# Iridium_9603_Beacon_V5M.net
KiCad netlist of a schematic drawn in EAGLE
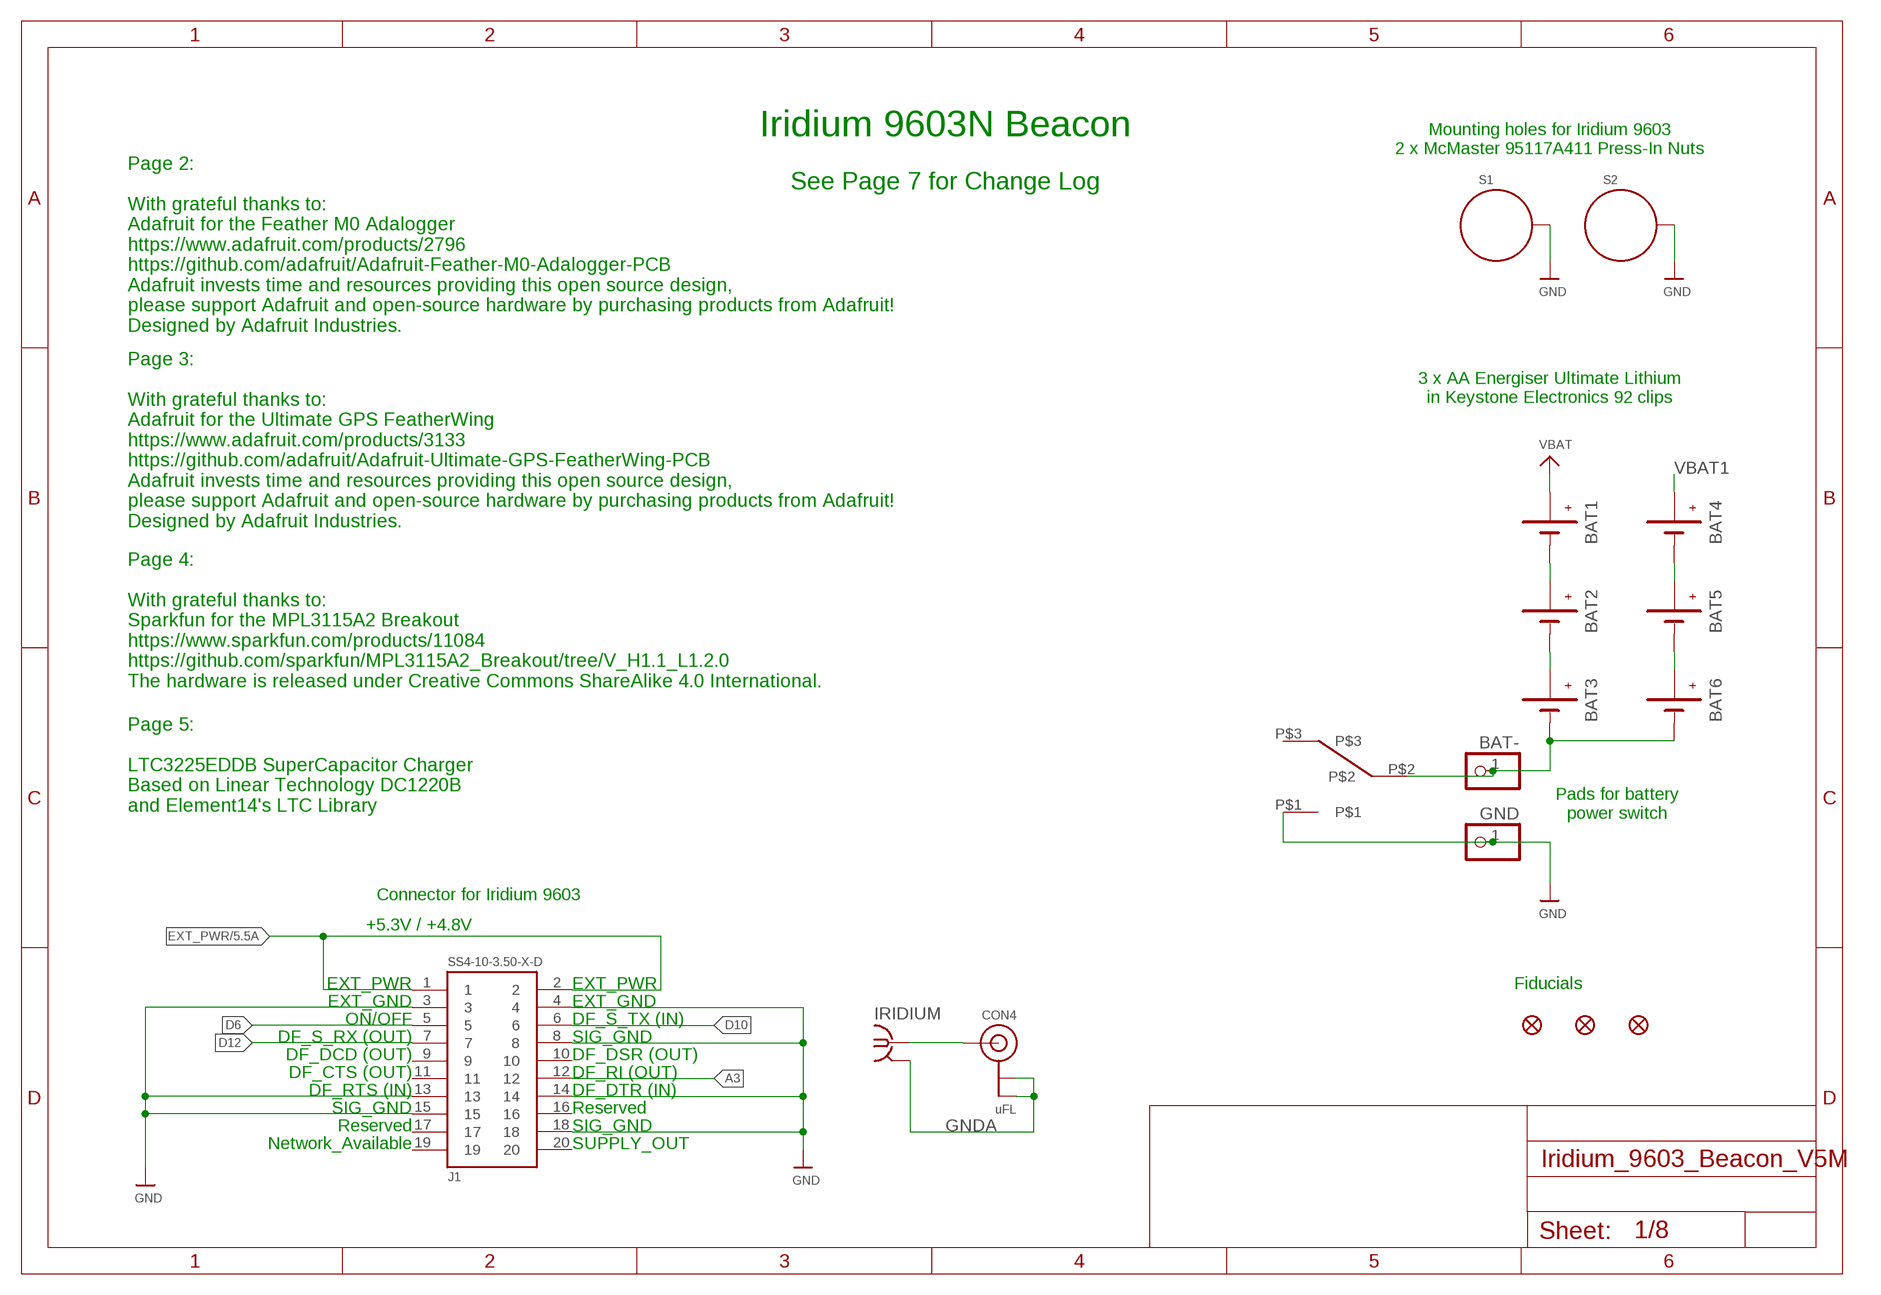
[diagram p0: schematic, sheet 1]
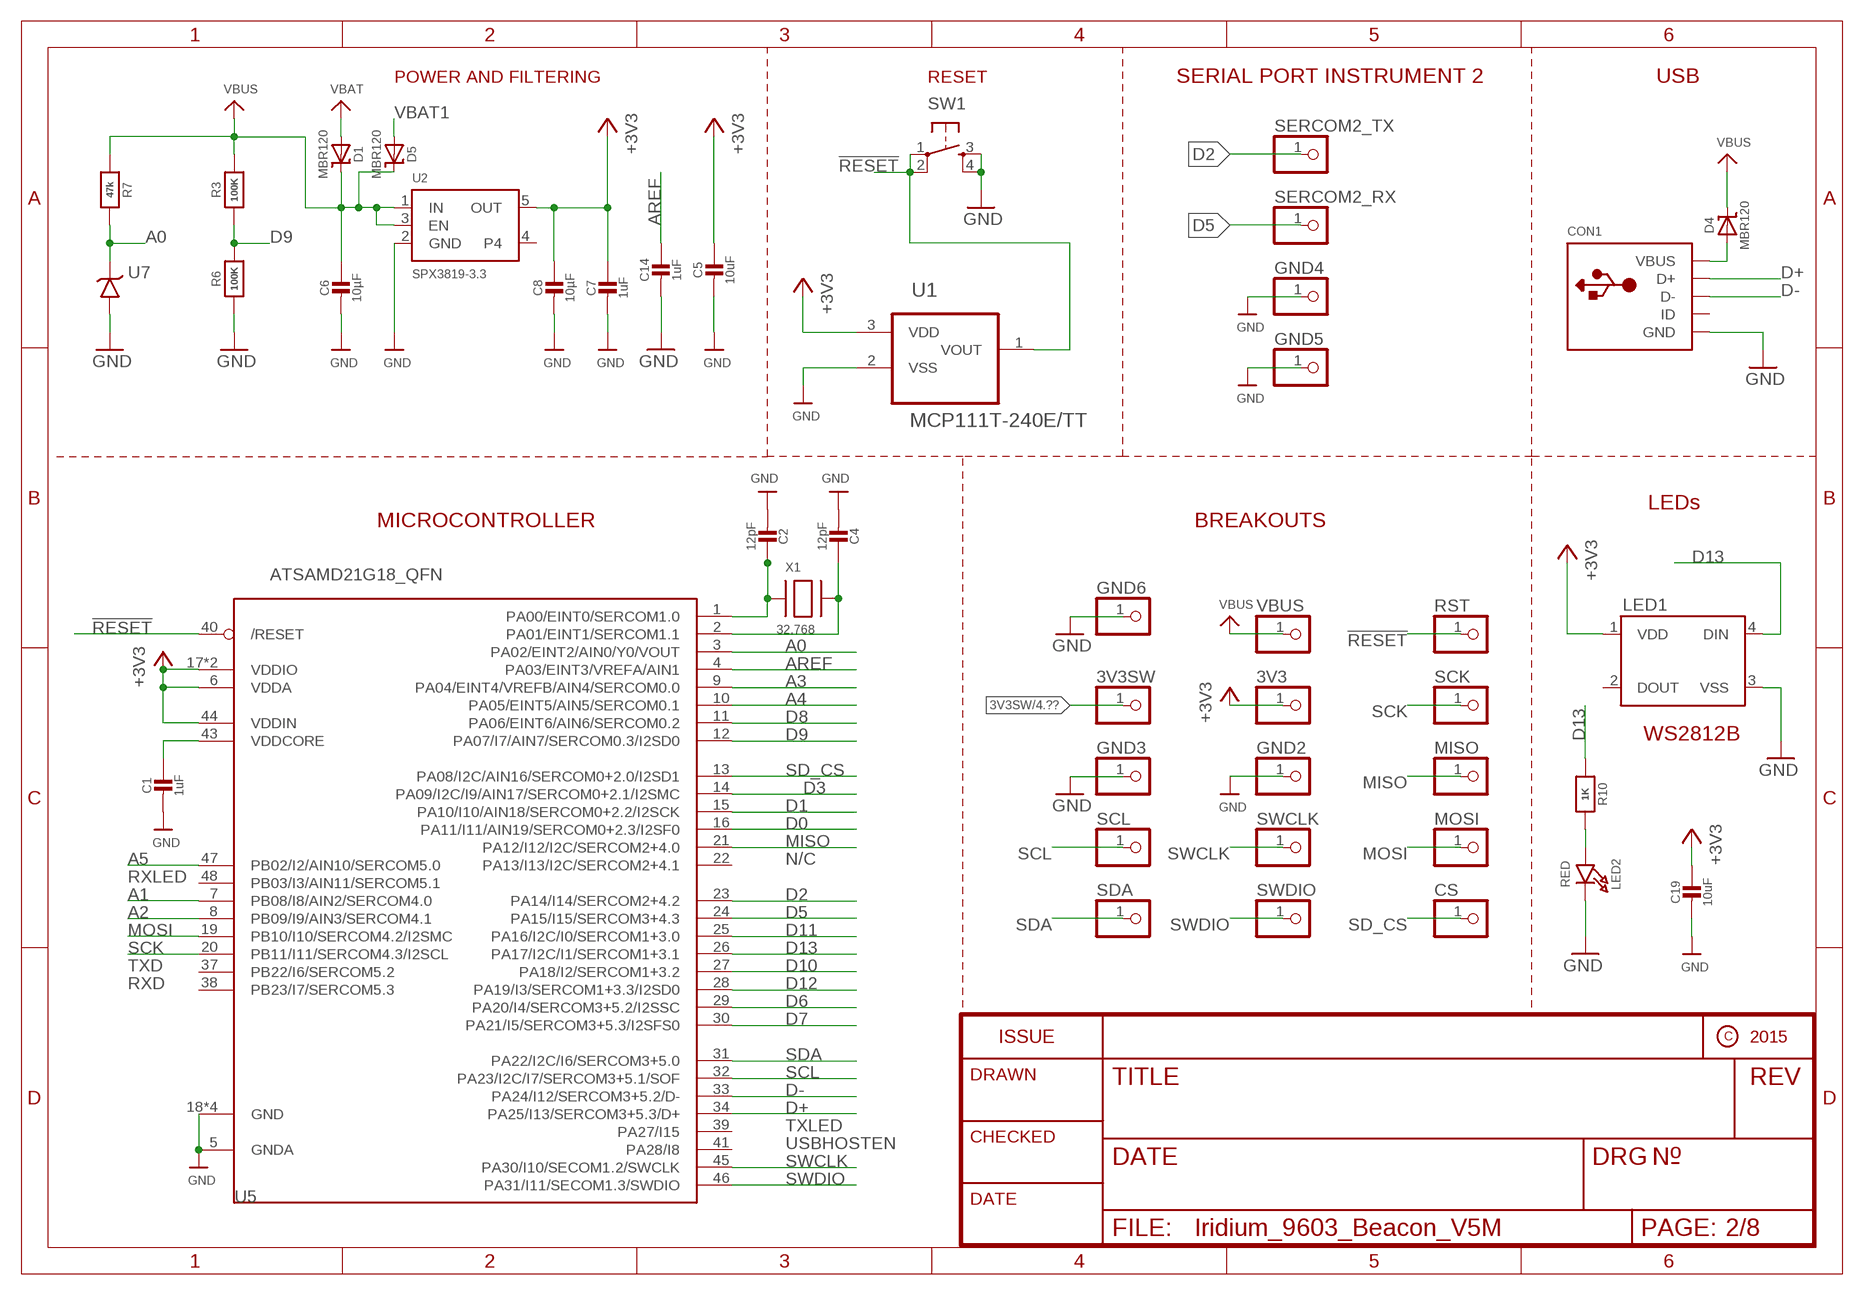
[diagram p1: schematic, sheet 2]
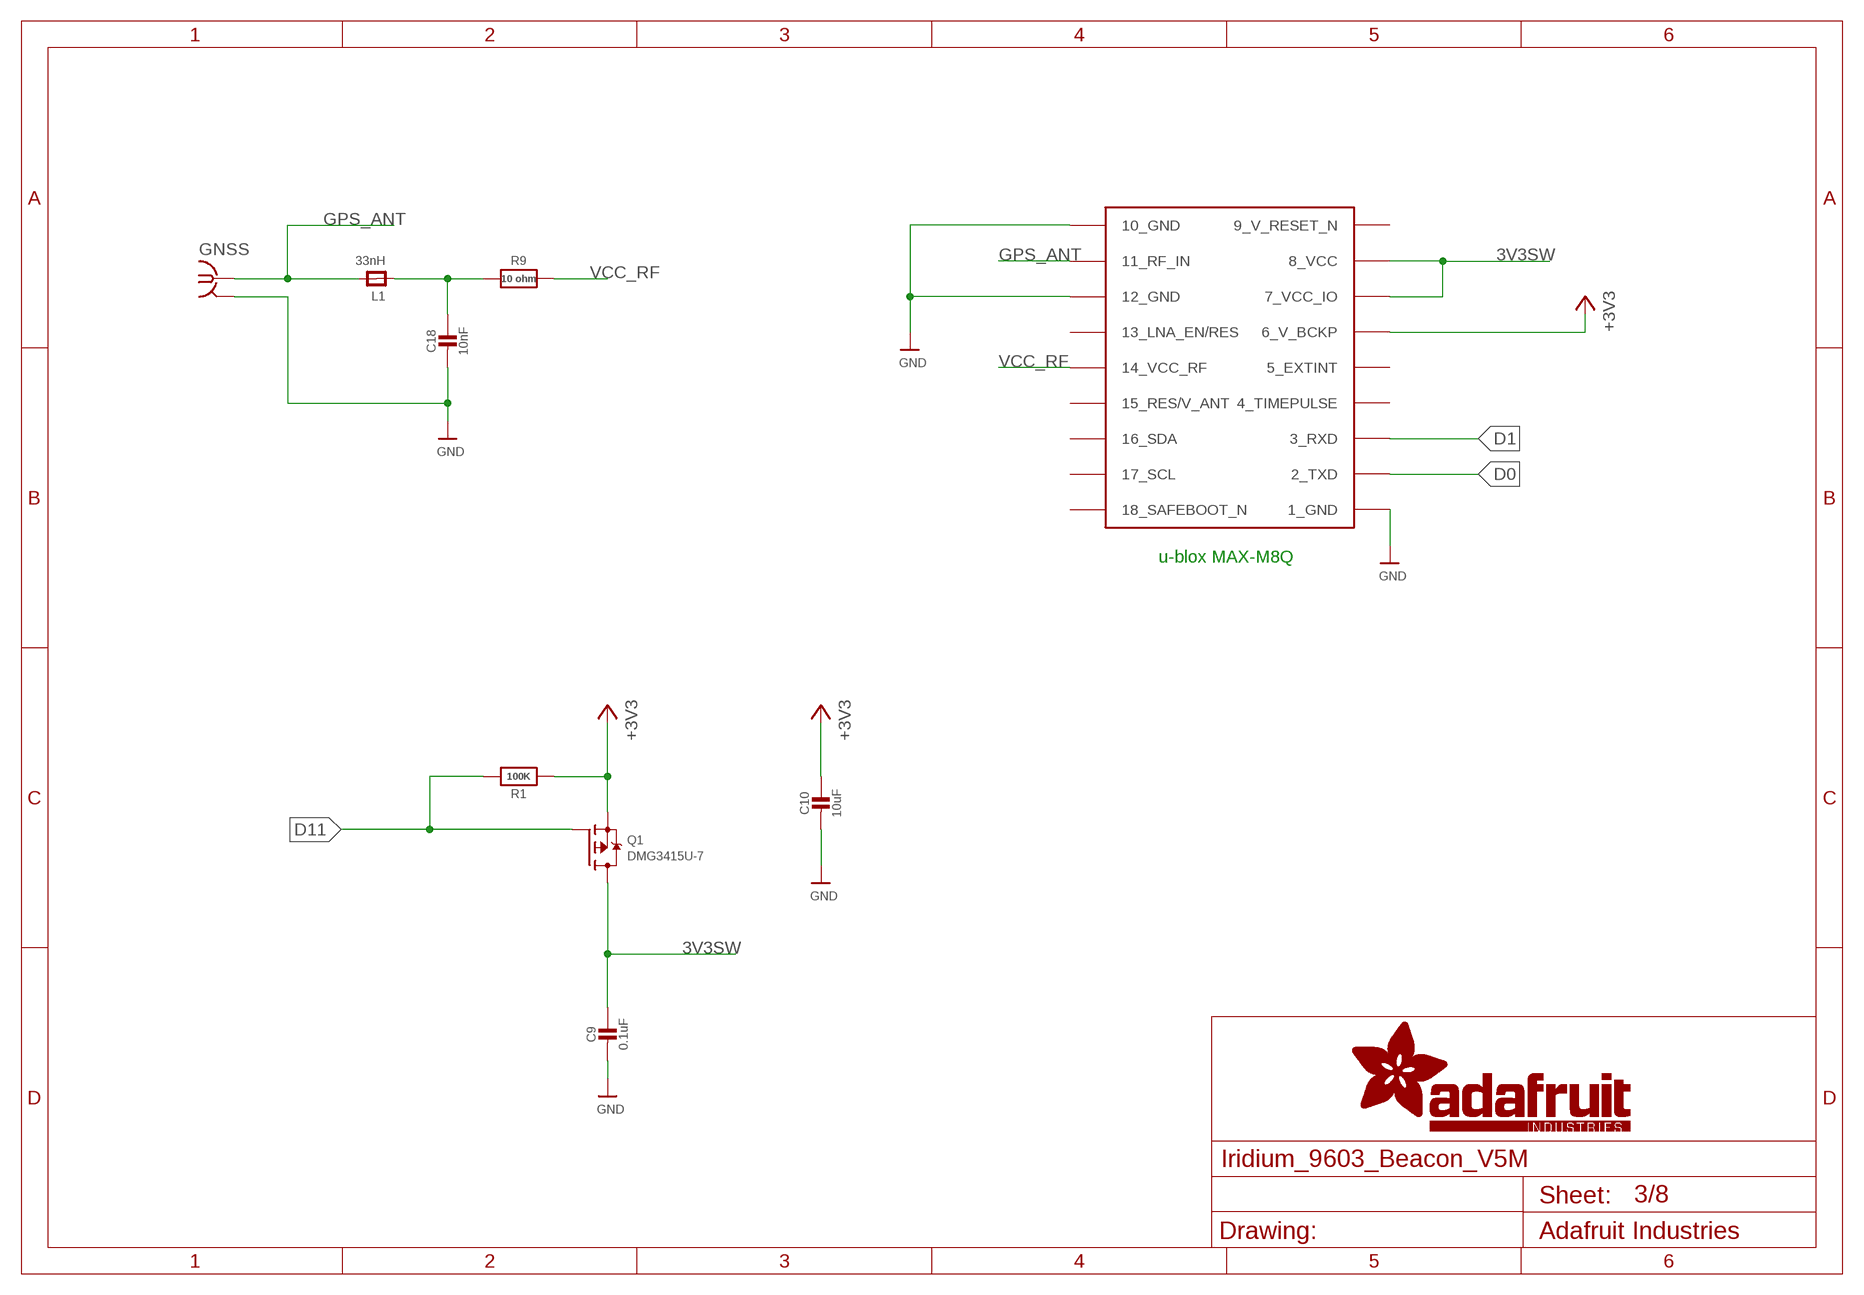
[diagram p2: schematic, sheet 3]
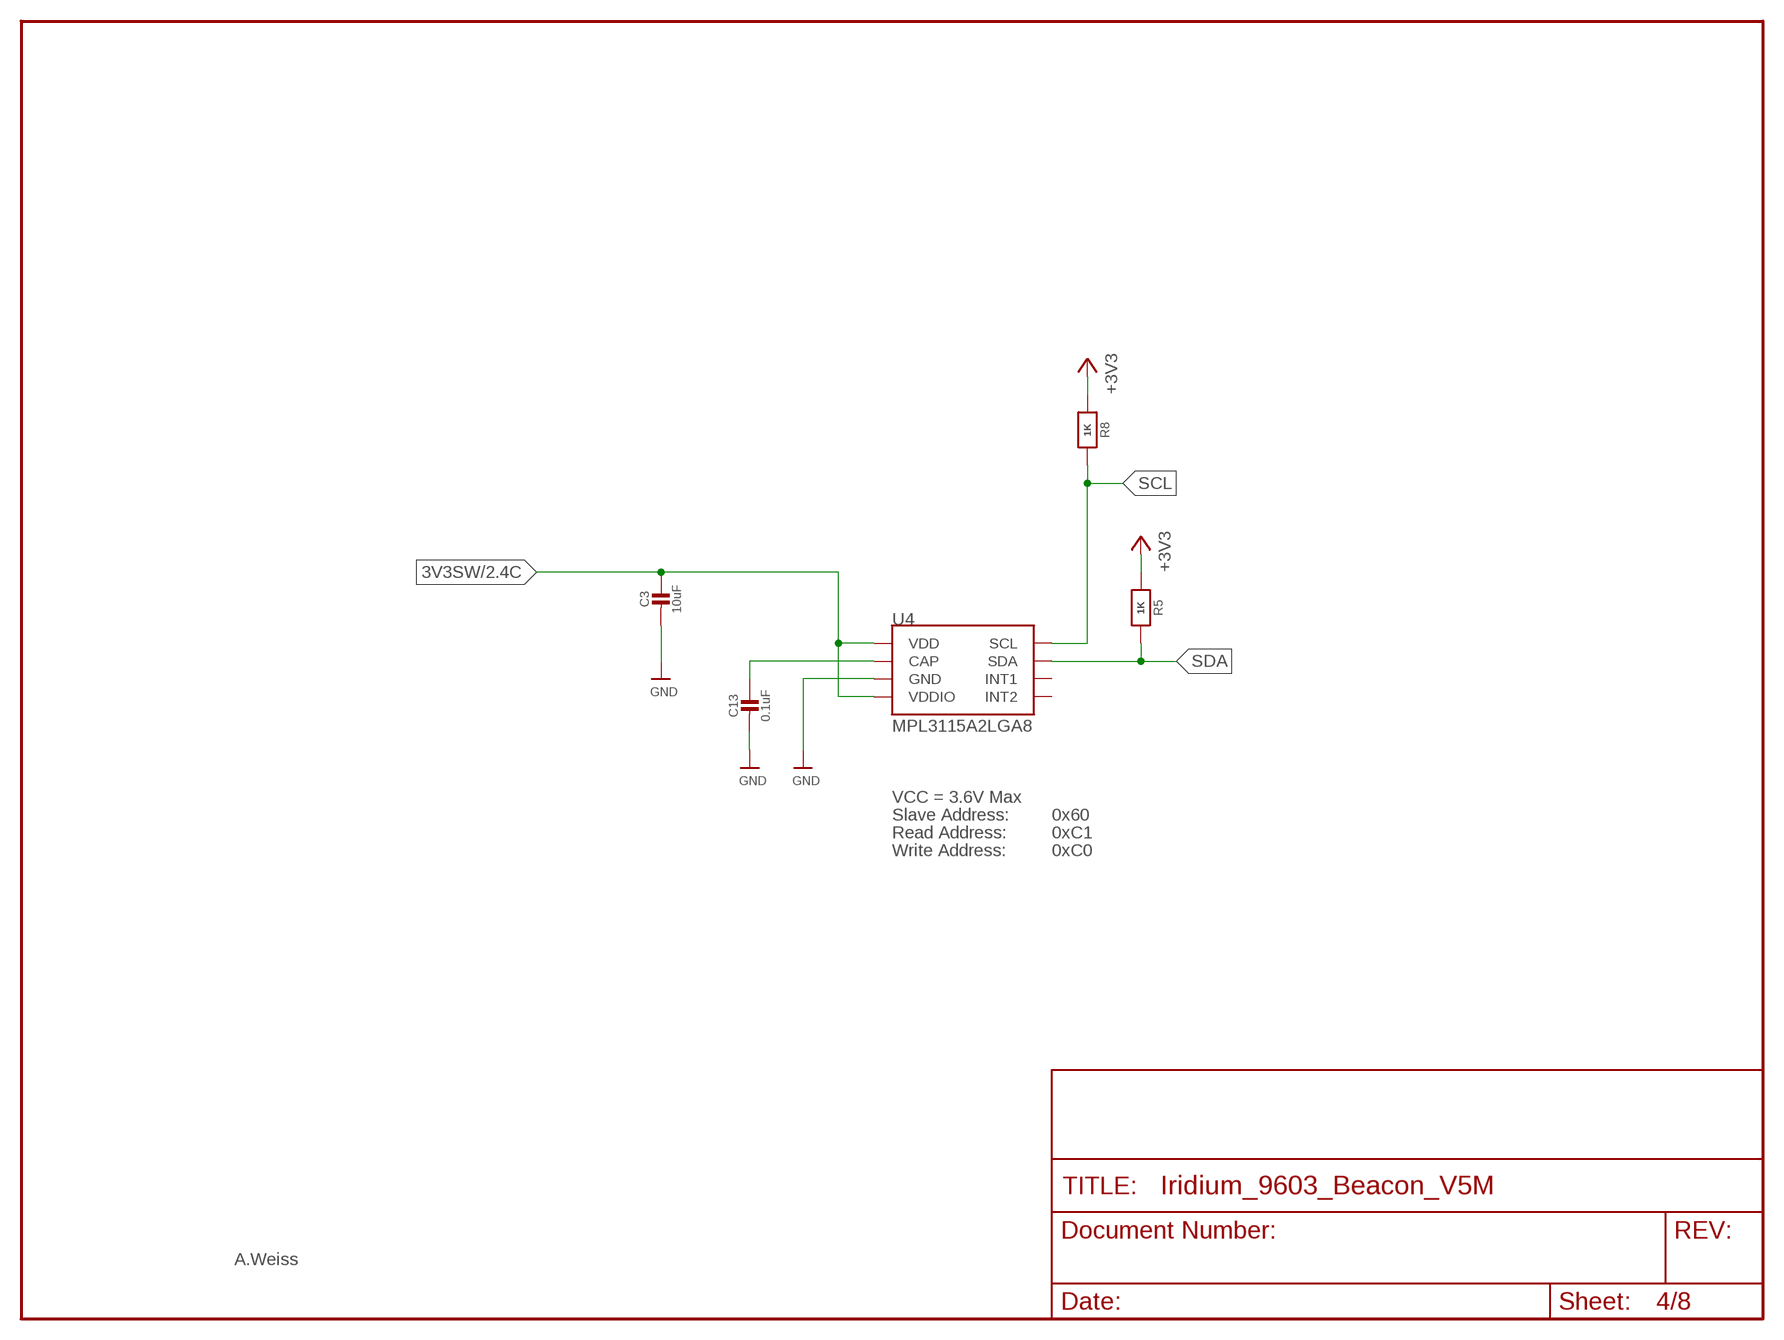
[diagram p3: schematic, sheet 4]
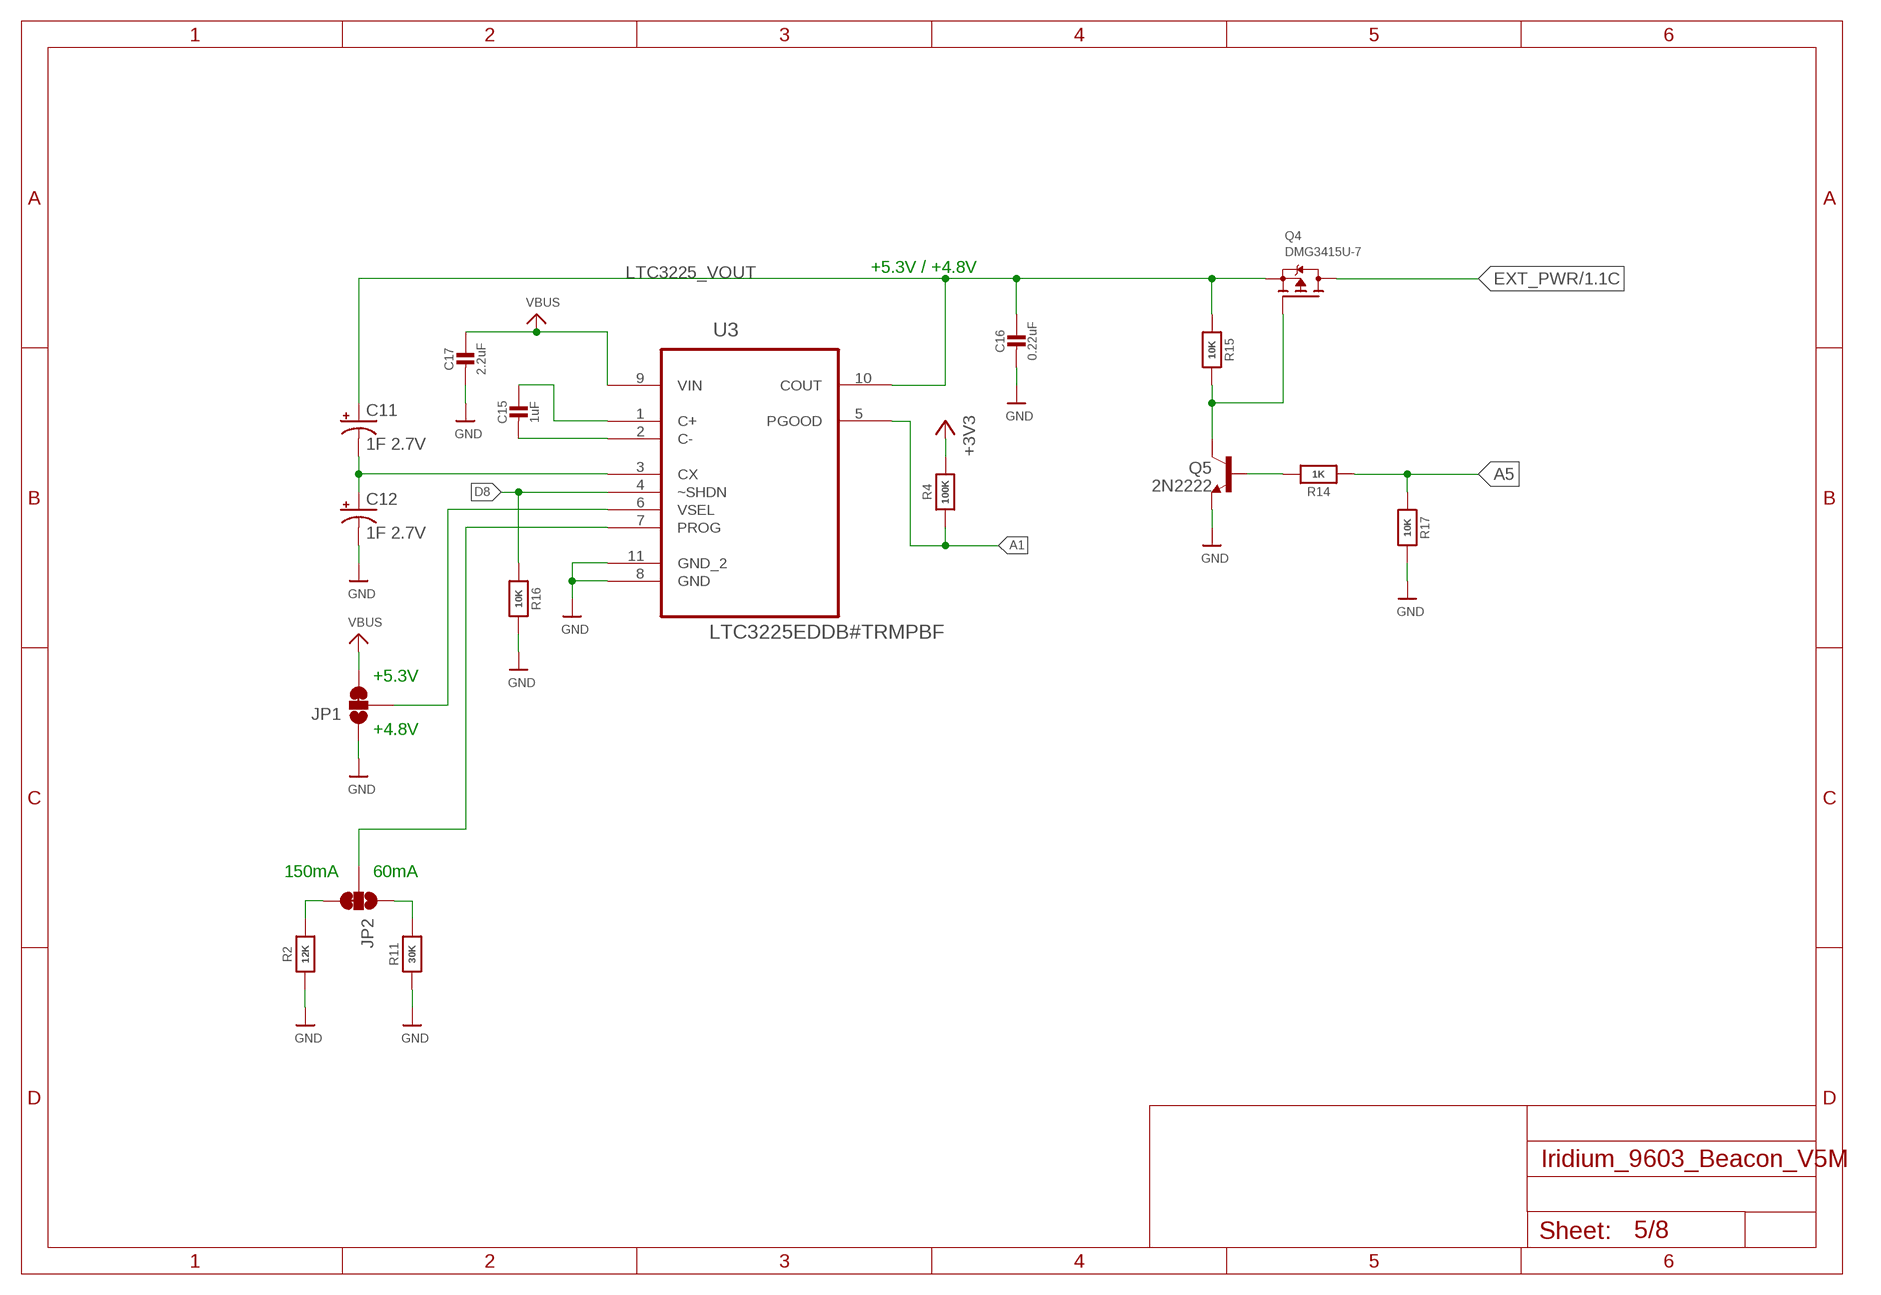
[diagram p4: schematic, sheet 5]
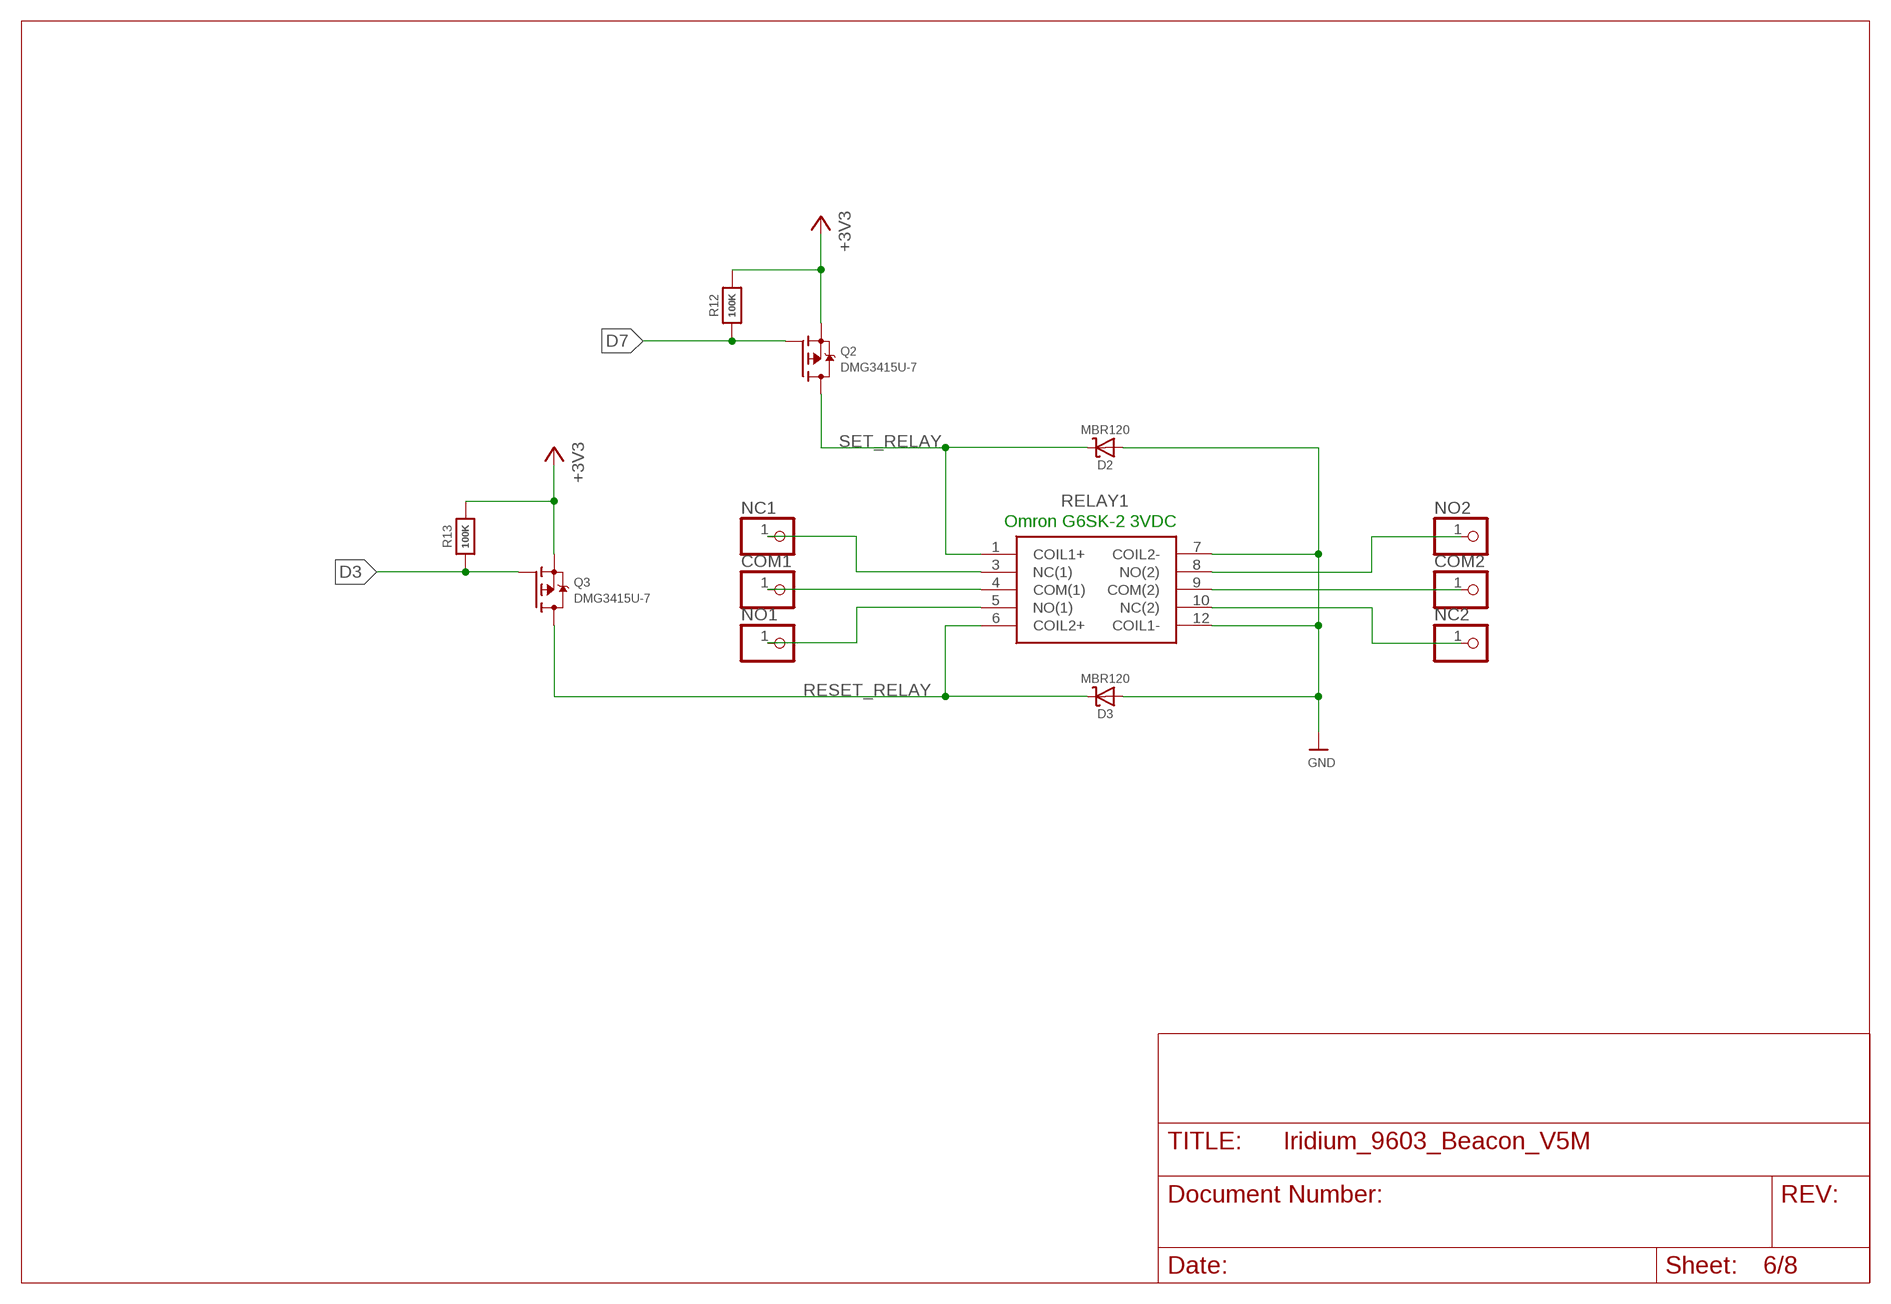
[diagram p5: schematic, sheet 6]
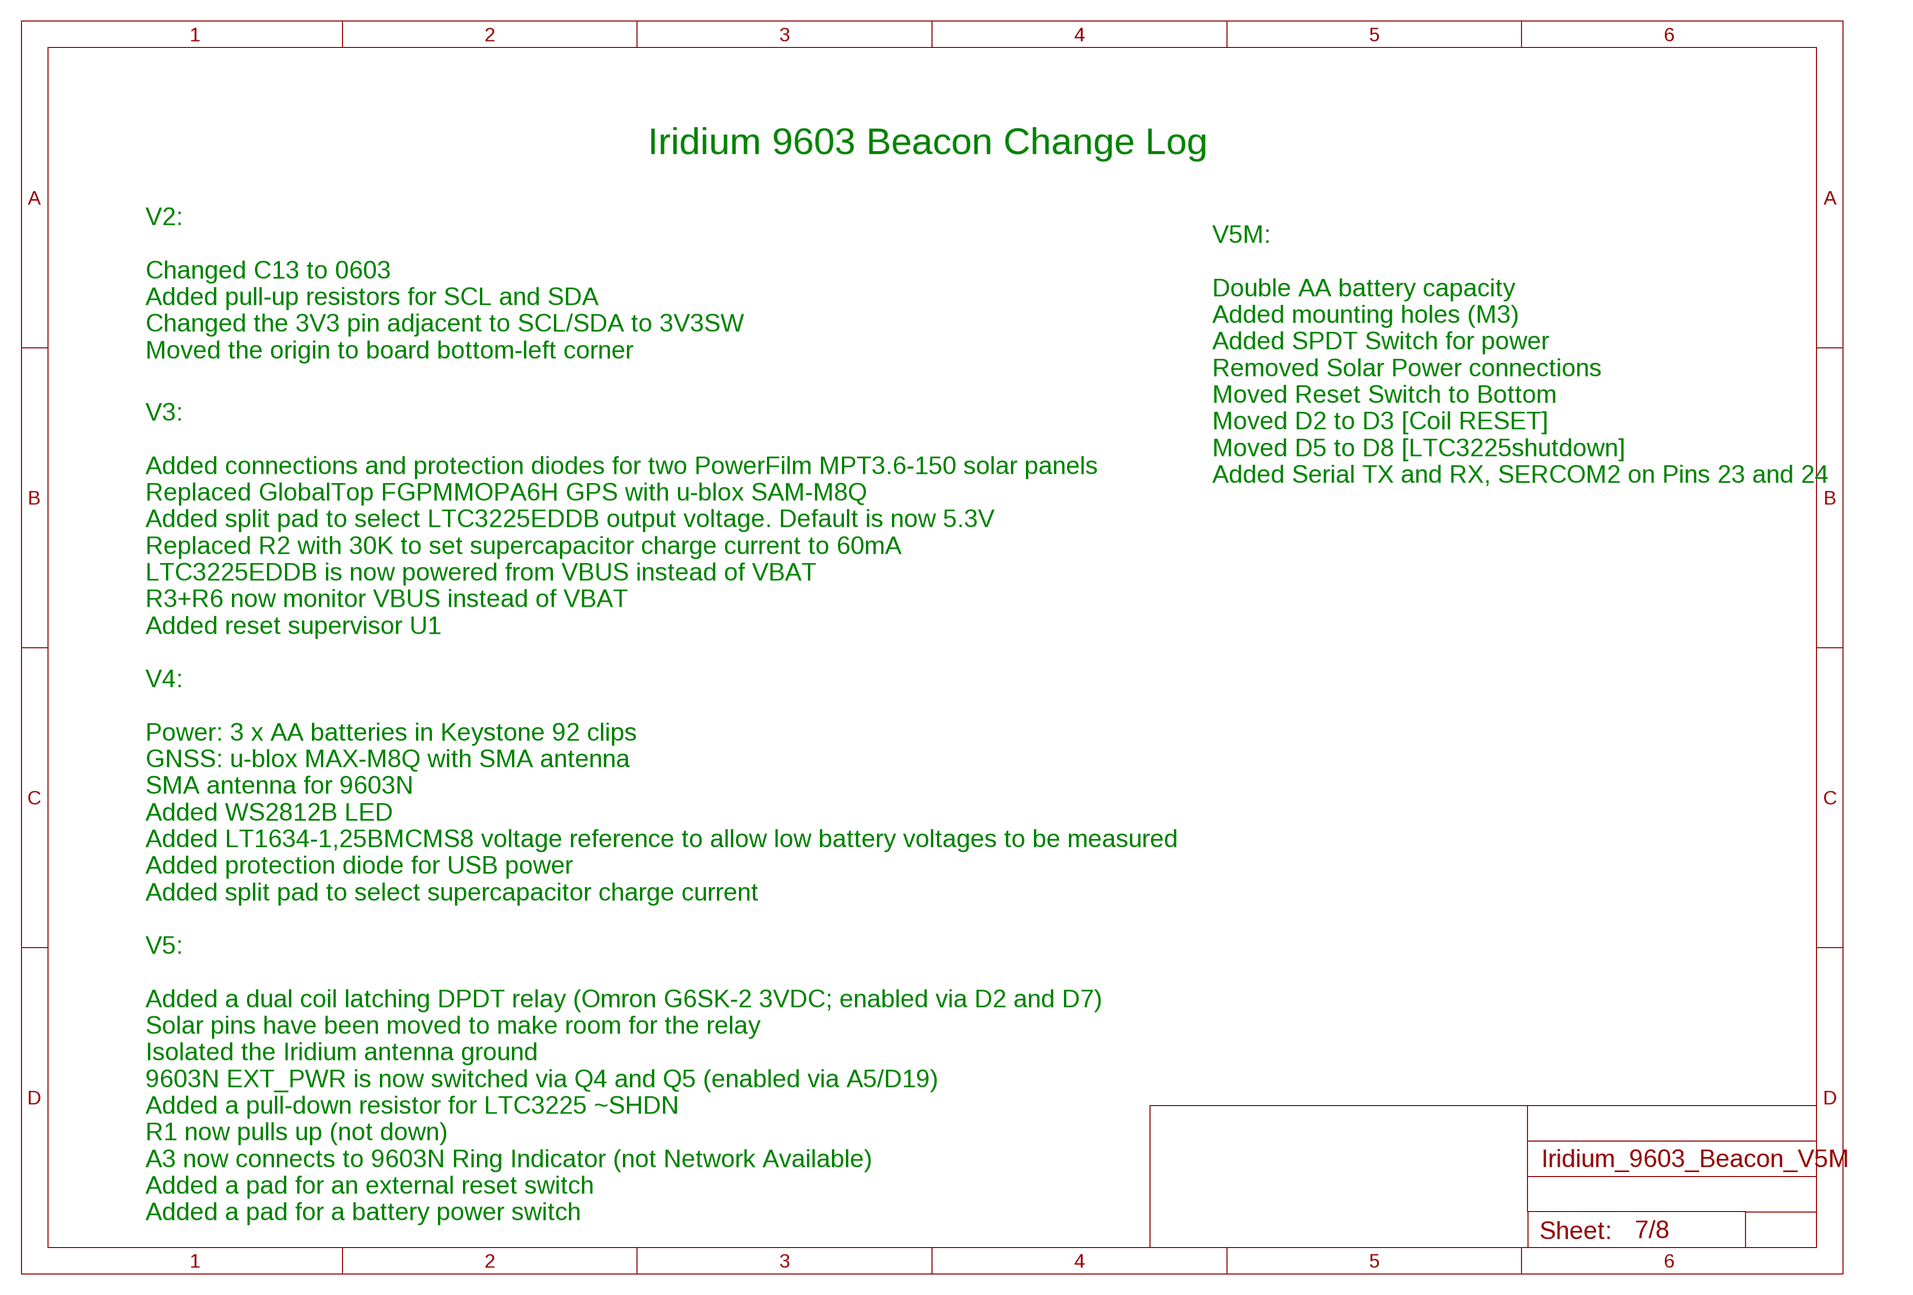
[diagram p6: schematic, sheet 7]
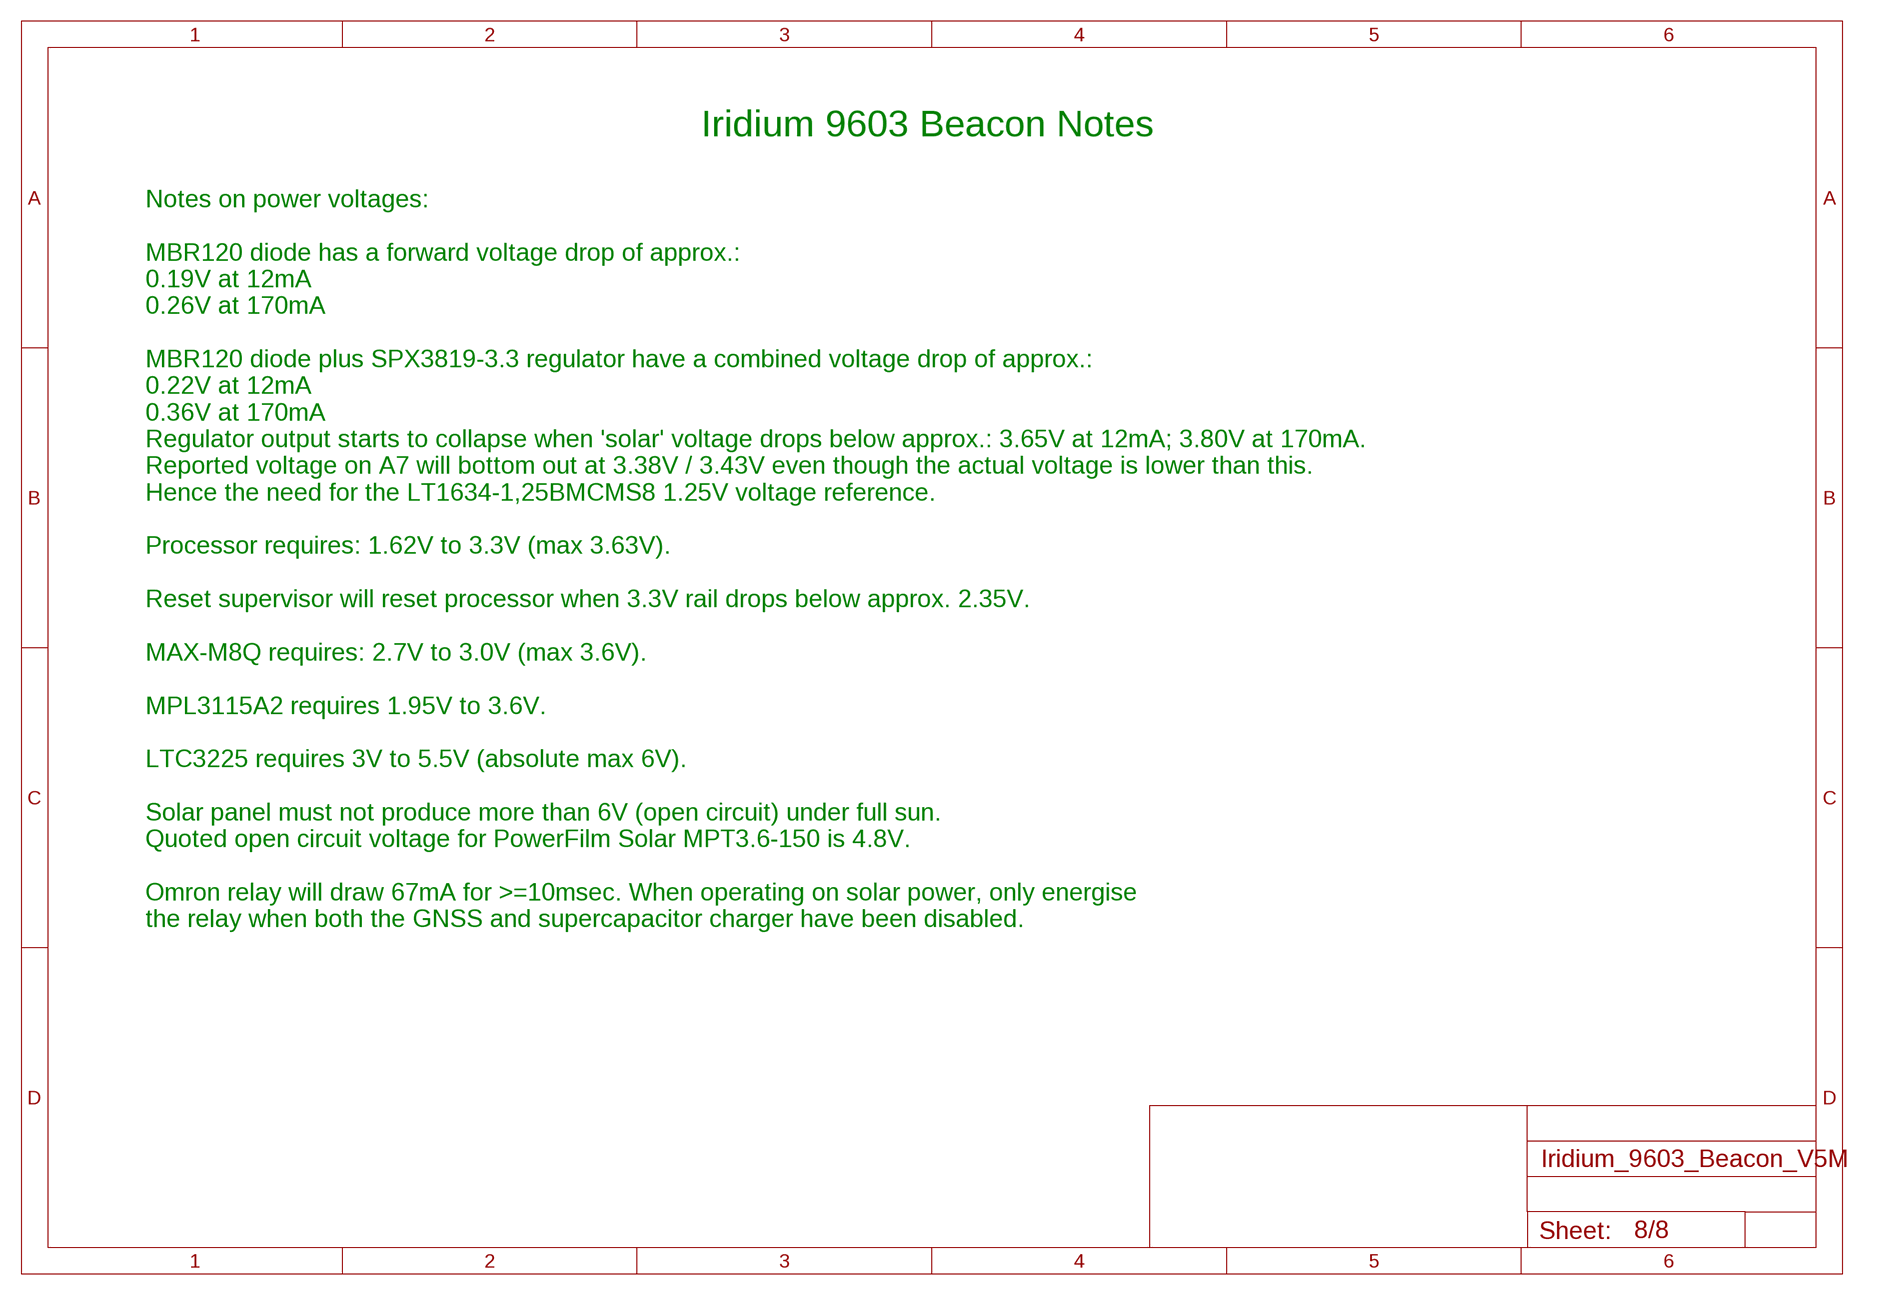
[diagram p7: schematic, sheet 8]

(export (version "E")
  (design (tool "Eeschema 10.0.6"))
  (components
    (comp (ref "C3")
      (value "10uF")
      (footprint "eagle-import:0805-NO")
      (libsource (lib "eagle-import") (part "CAP_CERAMIC0805-NOOUTLINE"))
    )
    (comp (ref "C13")
      (value "0.1uF")
      (footprint "eagle-import:0805-NO")
      (libsource (lib "eagle-import") (part "CAP_CERAMIC0805-NOOUTLINE"))
    )
    (comp (ref "R5")
      (value "1K")
      (footprint "eagle-import:0603-NO")
      (libsource (lib "eagle-import") (part "RESISTOR_0603_NOOUT"))
    )
    (comp (ref "R8")
      (value "1K")
      (footprint "eagle-import:0603-NO")
      (libsource (lib "eagle-import") (part "RESISTOR_0603_NOOUT"))
    )
    (comp (ref "U4")
      (value "MPL3115A2LGA8")
      (footprint "eagle-import:LGA8")
      (libsource (lib "eagle-import") (part "MPL3115A2LGA8"))
    )
    (comp (ref "BAT-")
      (value "PINHD-1X1")
      (footprint "eagle-import:1X01")
      (libsource (lib "eagle-import") (part "PINHD-1X1"))
    )
    (comp (ref "BAT1")
      (value "BATTERYKEYSTONE92")
      (footprint "eagle-import:BATTERY-AAA-KEYSTONE92")
      (libsource (lib "eagle-import") (part "BATTERYKEYSTONE92"))
    )
    (comp (ref "BAT2")
      (value "BATTERYKEYSTONE92")
      (footprint "eagle-import:BATTERY-AAA-KEYSTONE92")
      (libsource (lib "eagle-import") (part "BATTERYKEYSTONE92"))
    )
    (comp (ref "BAT3")
      (value "BATTERYKEYSTONE92")
      (footprint "eagle-import:BATTERY-AAA-KEYSTONE92")
      (libsource (lib "eagle-import") (part "BATTERYKEYSTONE92"))
    )
    (comp (ref "BAT4")
      (value "BATTERYKEYSTONE92")
      (footprint "eagle-import:BATTERY-AAA-KEYSTONE92")
      (libsource (lib "eagle-import") (part "BATTERYKEYSTONE92"))
    )
    (comp (ref "BAT5")
      (value "BATTERYKEYSTONE92")
      (footprint "eagle-import:BATTERY-AAA-KEYSTONE92")
      (libsource (lib "eagle-import") (part "BATTERYKEYSTONE92"))
    )
    (comp (ref "BAT6")
      (value "BATTERYKEYSTONE92")
      (footprint "eagle-import:BATTERY-AAA-KEYSTONE92")
      (libsource (lib "eagle-import") (part "BATTERYKEYSTONE92"))
    )
    (comp (ref "CON4")
      (value "uFL")
      (footprint "eagle-import:U.FL")
      (libsource (lib "eagle-import") (part "ANTENNA_U.FL"))
    )
    (comp (ref "FD1")
      (value "FIDUCIAL1X2")
      (footprint "eagle-import:FIDUCIAL-1X2")
      (libsource (lib "eagle-import") (part "FIDUCIAL1X2"))
    )
    (comp (ref "FD2")
      (value "FIDUCIAL1X2")
      (footprint "eagle-import:FIDUCIAL-1X2")
      (libsource (lib "eagle-import") (part "FIDUCIAL1X2"))
    )
    (comp (ref "FD3")
      (value "FIDUCIAL1X2")
      (footprint "eagle-import:FIDUCIAL-1X2")
      (libsource (lib "eagle-import") (part "FIDUCIAL1X2"))
    )
    (comp (ref "GND")
      (value "PINHD-1X1")
      (footprint "eagle-import:1X01")
      (libsource (lib "eagle-import") (part "PINHD-1X1"))
    )
    (comp (ref "IRIDIUM")
      (value "SMA-142-0711-821/826")
      (footprint "eagle-import:J502-ND-142-0711-821_826")
      (fields (field (name "MF") "JOHNSON COMPONENTS") (field (name "MPN") "142-0711-821"))
      (libsource (lib "eagle-import") (part "con-coax_133_SMA-142-0711-821/826"))
    )
    (comp (ref "J1")
      (value "SS4-10-3.50-X-D")
      (footprint "eagle-import:SS4-10-3.50-X-D")
      (libsource (lib "eagle-import") (part "SS4-10-3.50-X-D"))
    )
    (comp (ref "S1")
      (value "STANDOFF_ELECTRICALMCMASTER-95117A411")
      (footprint "eagle-import:STANDOFF-ELECTRICAL-MCMASTER-95117A411")
      (libsource (lib "eagle-import") (part "STANDOFF_ELECTRICALMCMASTER-95117A411"))
    )
    (comp (ref "S2")
      (value "STANDOFF_ELECTRICALMCMASTER-95117A411")
      (footprint "eagle-import:STANDOFF-ELECTRICAL-MCMASTER-95117A411")
      (libsource (lib "eagle-import") (part "STANDOFF_ELECTRICALMCMASTER-95117A411"))
    )
    (comp (ref "U53")
      (value "7101K2AV2QE")
      (footprint "eagle-import:AV2_SPDT")
      (libsource (lib "eagle-import") (part "7101K2AV2QE"))
    )
    (comp (ref "C11")
      (value "1F 2.7V")
      (footprint "eagle-import:CPOL-RADIAL-1F-2.7V")
      (libsource (lib "eagle-import") (part "1F-2.7V(PTH)CPOL-RADIAL-1H-2.7V"))
    )
    (comp (ref "C12")
      (value "1F 2.7V")
      (footprint "eagle-import:CPOL-RADIAL-1F-2.7V")
      (libsource (lib "eagle-import") (part "1F-2.7V(PTH)CPOL-RADIAL-1H-2.7V"))
    )
    (comp (ref "C15")
      (value "1uF")
      (footprint "eagle-import:0603-NO")
      (libsource (lib "eagle-import") (part "CAP_CERAMIC0603_NO"))
    )
    (comp (ref "C16")
      (value "0.22uF")
      (footprint "eagle-import:0603-NO")
      (libsource (lib "eagle-import") (part "CAP_CERAMIC0603_NO"))
    )
    (comp (ref "C17")
      (value "2.2uF")
      (footprint "eagle-import:0805-NO")
      (libsource (lib "eagle-import") (part "CAP_CERAMIC0805-NOOUTLINE"))
    )
    (comp (ref "JP1")
      (value "JUMPER-PAD-3-2OF3_NC_BY_TRACE_LARGE")
      (footprint "eagle-import:PAD-JUMPER-3-2OF3_NC_BY_TRACE_YES_SILK_LARGE")
      (libsource (lib "eagle-import") (part "JUMPER-PAD-3-2OF3_NC_BY_TRACE_LARGE"))
    )
    (comp (ref "JP2")
      (value "JUMPER-PAD-3-2OF3_NC_BY_TRACE_LARGE")
      (footprint "eagle-import:PAD-JUMPER-3-2OF3_NC_BY_TRACE_YES_SILK_LARGE")
      (libsource (lib "eagle-import") (part "JUMPER-PAD-3-2OF3_NC_BY_TRACE_LARGE"))
    )
    (comp (ref "Q4")
      (value "DMG3415U-7")
      (footprint "eagle-import:SOT23-WIDE")
      (libsource (lib "eagle-import") (part "MOSFET-PWIDE"))
    )
    (comp (ref "Q5")
      (value "2N2222")
      (footprint "eagle-import:SOT23-BEC")
      (libsource (lib "eagle-import") (part "-NPN-SOT23-BECMMBT2222ALT1"))
    )
    (comp (ref "R2")
      (value "12K")
      (footprint "eagle-import:0805-NO")
      (libsource (lib "eagle-import") (part "RESISTOR0805_NOOUTLINE"))
    )
    (comp (ref "R4")
      (value "100K")
      (footprint "eagle-import:0805-NO")
      (libsource (lib "eagle-import") (part "RESISTOR0805_NOOUTLINE"))
    )
    (comp (ref "R11")
      (value "30K")
      (footprint "eagle-import:0805-NO")
      (libsource (lib "eagle-import") (part "RESISTOR0805_NOOUTLINE"))
    )
    (comp (ref "R14")
      (value "1K")
      (footprint "eagle-import:0603-NO")
      (libsource (lib "eagle-import") (part "RESISTOR_0603_NOOUT"))
    )
    (comp (ref "R15")
      (value "10K")
      (footprint "eagle-import:0603-NO")
      (libsource (lib "eagle-import") (part "RESISTOR_0603_NOOUT"))
    )
    (comp (ref "R16")
      (value "10K")
      (footprint "eagle-import:0603-NO")
      (libsource (lib "eagle-import") (part "RESISTOR_0603_NOOUT"))
    )
    (comp (ref "R17")
      (value "10K")
      (footprint "eagle-import:0603-NO")
      (libsource (lib "eagle-import") (part "RESISTOR_0603_NOOUT"))
    )
    (comp (ref "U3")
      (value "LTC3225EDDB#TRMPBF")
      (footprint "eagle-import:DFN300X200-10L")
      (libsource (lib "eagle-import") (part "LTC3225EDDB-TRMPBFDFN300X200-10L"))
    )
    (comp (ref "3V3")
      (value "PINHD-1X1")
      (footprint "eagle-import:1X01")
      (libsource (lib "eagle-import") (part "PINHD-1X1"))
    )
    (comp (ref "3V3SW")
      (value "PINHD-1X1")
      (footprint "eagle-import:1X01")
      (libsource (lib "eagle-import") (part "PINHD-1X1"))
    )
    (comp (ref "C1")
      (value "1uF")
      (footprint "eagle-import:0603-NO")
      (libsource (lib "eagle-import") (part "CAP_CERAMIC0603_NO"))
    )
    (comp (ref "C2")
      (value "12pF")
      (footprint "eagle-import:0603-NO")
      (libsource (lib "eagle-import") (part "CAP_CERAMIC0603_NO"))
    )
    (comp (ref "C4")
      (value "12pF")
      (footprint "eagle-import:0603-NO")
      (libsource (lib "eagle-import") (part "CAP_CERAMIC0603_NO"))
    )
    (comp (ref "C5")
      (value "10uF")
      (footprint "eagle-import:0805-NO")
      (libsource (lib "eagle-import") (part "CAP_CERAMIC0805-NOOUTLINE"))
    )
    (comp (ref "C6")
      (value "10µF")
      (footprint "eagle-import:0805-NO")
      (libsource (lib "eagle-import") (part "CAP_CERAMIC0805-NOOUTLINE"))
    )
    (comp (ref "C7")
      (value "1uF")
      (footprint "eagle-import:0603-NO")
      (libsource (lib "eagle-import") (part "CAP_CERAMIC0603_NO"))
    )
    (comp (ref "C8")
      (value "10µF")
      (footprint "eagle-import:0805-NO")
      (libsource (lib "eagle-import") (part "CAP_CERAMIC0805-NOOUTLINE"))
    )
    (comp (ref "C14")
      (value "1uF")
      (footprint "eagle-import:0603-NO")
      (libsource (lib "eagle-import") (part "CAP_CERAMIC0603_NO"))
    )
    (comp (ref "C19")
      (value "10uF")
      (footprint "eagle-import:0805-NO")
      (libsource (lib "eagle-import") (part "CAP_CERAMIC0805-NOOUTLINE"))
    )
    (comp (ref "CON1")
      (value "USBFCI_10103594")
      (footprint "eagle-import:FCI_10103594")
      (libsource (lib "eagle-import") (part "USBFCI_10103594"))
    )
    (comp (ref "CS")
      (value "PINHD-1X1")
      (footprint "eagle-import:1X01")
      (libsource (lib "eagle-import") (part "PINHD-1X1"))
    )
    (comp (ref "D1")
      (value "MBR120")
      (footprint "eagle-import:SOD-123")
      (libsource (lib "eagle-import") (part "DIODE-SCHOTTKYSOD-123"))
    )
    (comp (ref "D4")
      (value "MBR120")
      (footprint "eagle-import:SOD-123")
      (libsource (lib "eagle-import") (part "DIODE-SCHOTTKYSOD-123"))
    )
    (comp (ref "D5")
      (value "MBR120")
      (footprint "eagle-import:SOD-123")
      (libsource (lib "eagle-import") (part "DIODE-SCHOTTKYSOD-123"))
    )
    (comp (ref "GND2")
      (value "PINHD-1X1")
      (footprint "eagle-import:1X01")
      (libsource (lib "eagle-import") (part "PINHD-1X1"))
    )
    (comp (ref "GND3")
      (value "PINHD-1X1")
      (footprint "eagle-import:1X01")
      (libsource (lib "eagle-import") (part "PINHD-1X1"))
    )
    (comp (ref "GND4")
      (value "PINHD-1X1")
      (footprint "eagle-import:1X01")
      (libsource (lib "eagle-import") (part "PINHD-1X1"))
    )
    (comp (ref "GND5")
      (value "PINHD-1X1")
      (footprint "eagle-import:1X01")
      (libsource (lib "eagle-import") (part "PINHD-1X1"))
    )
    (comp (ref "GND6")
      (value "PINHD-1X1")
      (footprint "eagle-import:1X01")
      (libsource (lib "eagle-import") (part "PINHD-1X1"))
    )
    (comp (ref "LED1")
      (value "WS2812B")
      (footprint "eagle-import:WS2812B")
      (libsource (lib "eagle-import") (part "WS2812B"))
    )
    (comp (ref "LED2")
      (value "RED")
      (footprint "eagle-import:CHIPLED_0805_NOOUTLINE")
      (libsource (lib "eagle-import") (part "LED0805_NOOUTLINE"))
    )
    (comp (ref "MISO")
      (value "PINHD-1X1")
      (footprint "eagle-import:1X01")
      (libsource (lib "eagle-import") (part "PINHD-1X1"))
    )
    (comp (ref "MOSI")
      (value "PINHD-1X1")
      (footprint "eagle-import:1X01")
      (libsource (lib "eagle-import") (part "PINHD-1X1"))
    )
    (comp (ref "R3")
      (value "100K")
      (footprint "eagle-import:0805-NO")
      (libsource (lib "eagle-import") (part "RESISTOR0805_NOOUTLINE"))
    )
    (comp (ref "R6")
      (value "100K")
      (footprint "eagle-import:0805-NO")
      (libsource (lib "eagle-import") (part "RESISTOR0805_NOOUTLINE"))
    )
    (comp (ref "R7")
      (value "47k")
      (footprint "eagle-import:0603-NO")
      (libsource (lib "eagle-import") (part "RESISTOR_0603_NOOUT"))
    )
    (comp (ref "R10")
      (value "1K")
      (footprint "eagle-import:0603-NO")
      (libsource (lib "eagle-import") (part "RESISTOR_0603_NOOUT"))
    )
    (comp (ref "RST")
      (value "PINHD-1X1")
      (footprint "eagle-import:1X01")
      (libsource (lib "eagle-import") (part "PINHD-1X1"))
    )
    (comp (ref "SCK")
      (value "PINHD-1X1")
      (footprint "eagle-import:1X01")
      (libsource (lib "eagle-import") (part "PINHD-1X1"))
    )
    (comp (ref "SCL")
      (value "PINHD-1X1")
      (footprint "eagle-import:1X01")
      (libsource (lib "eagle-import") (part "PINHD-1X1"))
    )
    (comp (ref "SDA")
      (value "PINHD-1X1")
      (footprint "eagle-import:1X01")
      (libsource (lib "eagle-import") (part "PINHD-1X1"))
    )
    (comp (ref "SERCOM2_RX")
      (value "PINHD-1X1")
      (footprint "eagle-import:1X01")
      (libsource (lib "eagle-import") (part "PINHD-1X1"))
    )
    (comp (ref "SERCOM2_TX")
      (value "PINHD-1X1")
      (footprint "eagle-import:1X01")
      (libsource (lib "eagle-import") (part "PINHD-1X1"))
    )
    (comp (ref "SW1")
      (value "SWITCH_SPST_4_PINRECT")
      (footprint "eagle-import:TACTILE_SWITCH_SMD_4.6X2.8MM")
      (libsource (lib "eagle-import") (part "SWITCH_SPST_4_PINRECT"))
    )
    (comp (ref "SWCLK")
      (value "PINHD-1X1")
      (footprint "eagle-import:1X01")
      (libsource (lib "eagle-import") (part "PINHD-1X1"))
    )
    (comp (ref "SWDIO")
      (value "PINHD-1X1")
      (footprint "eagle-import:1X01")
      (libsource (lib "eagle-import") (part "PINHD-1X1"))
    )
    (comp (ref "U1")
      (value "MCP111T-240E/TT")
      (footprint "eagle-import:SOT95P237X112-3N")
      (fields (field (name "MPN") "MCP111T-270E/TT") (field (name "MPN_1") "MCP111T-240E/TT"))
      (libsource (lib "eagle-import") (part "MCP111T-270E/TT"))
    )
    (comp (ref "U2")
      (value "SPX3819-3.3")
      (footprint "eagle-import:SOT23-5")
      (libsource (lib "eagle-import") (part "VREG_SOT23-5"))
    )
    (comp (ref "U5")
      (value "ATSAMD21G18_QFN")
      (footprint "eagle-import:TQFN48_7MM")
      (libsource (lib "eagle-import") (part "ATSAMD21J_QFN"))
    )
    (comp (ref "U7")
      (value "LT1634-1,25BMCMS8")
      (footprint "eagle-import:MSOP8")
      (libsource (lib "eagle-import") (part "LT1634BMCMS8-1,25"))
    )
    (comp (ref "VBUS")
      (value "PINHD-1X1")
      (footprint "eagle-import:1X01")
      (libsource (lib "eagle-import") (part "PINHD-1X1"))
    )
    (comp (ref "X1")
      (value "32.768")
      (footprint "eagle-import:XTAL3215")
      (libsource (lib "eagle-import") (part "XTAL-3.2X1.5"))
    )
    (comp (ref "C9")
      (value "0.1uF")
      (footprint "eagle-import:0805-NO")
      (libsource (lib "eagle-import") (part "CAP_CERAMIC0805-NOOUTLINE"))
    )
    (comp (ref "C10")
      (value "10uF")
      (footprint "eagle-import:0805-NO")
      (libsource (lib "eagle-import") (part "CAP_CERAMIC0805-NOOUTLINE"))
    )
    (comp (ref "C18")
      (value "10nF")
      (footprint "eagle-import:0805-NO")
      (libsource (lib "eagle-import") (part "CAP_CERAMIC0805-NOOUTLINE"))
    )
    (comp (ref "GNSS")
      (value "SMA-142-0711-821/826")
      (footprint "eagle-import:J502-ND-142-0711-821_826")
      (fields (field (name "MF") "JOHNSON COMPONENTS") (field (name "MPN") "142-0711-821"))
      (libsource (lib "eagle-import") (part "SMA-142-0711-821/826"))
    )
    (comp (ref "L1")
      (value "33nH")
      (footprint "eagle-import:0805-NO")
      (libsource (lib "eagle-import") (part "FERRITE-0805NO"))
    )
    (comp (ref "Q1")
      (value "DMG3415U-7")
      (footprint "eagle-import:SOT23-WIDE")
      (libsource (lib "eagle-import") (part "MOSFET-PWIDE"))
    )
    (comp (ref "R1")
      (value "100K")
      (footprint "eagle-import:0805-NO")
      (libsource (lib "eagle-import") (part "RESISTOR0805_NOOUTLINE"))
    )
    (comp (ref "R9")
      (value "10 ohm")
      (footprint "eagle-import:0805-NO")
      (libsource (lib "eagle-import") (part "RESISTOR0805_NOOUTLINE"))
    )
    (comp (ref "U6")
      (value "MAX-M8")
      (footprint "eagle-import:MAX-M8")
      (libsource (lib "eagle-import") (part "MAX-M8"))
    )
    (comp (ref "COM1")
      (value "PINHD-1X1")
      (footprint "eagle-import:1X01")
      (libsource (lib "eagle-import") (part "PINHD-1X1"))
    )
    (comp (ref "COM2")
      (value "PINHD-1X1")
      (footprint "eagle-import:1X01")
      (libsource (lib "eagle-import") (part "PINHD-1X1"))
    )
    (comp (ref "D2")
      (value "MBR120")
      (footprint "eagle-import:SOD-123")
      (libsource (lib "eagle-import") (part "DIODE-SCHOTTKYSOD-123"))
    )
    (comp (ref "D3")
      (value "MBR120")
      (footprint "eagle-import:SOD-123")
      (libsource (lib "eagle-import") (part "DIODE-SCHOTTKYSOD-123"))
    )
    (comp (ref "NC1")
      (value "PINHD-1X1")
      (footprint "eagle-import:1X01")
      (libsource (lib "eagle-import") (part "PINHD-1X1"))
    )
    (comp (ref "NC2")
      (value "PINHD-1X1")
      (footprint "eagle-import:1X01")
      (libsource (lib "eagle-import") (part "PINHD-1X1"))
    )
    (comp (ref "NO1")
      (value "PINHD-1X1")
      (footprint "eagle-import:1X01")
      (libsource (lib "eagle-import") (part "PINHD-1X1"))
    )
    (comp (ref "NO2")
      (value "PINHD-1X1")
      (footprint "eagle-import:1X01")
      (libsource (lib "eagle-import") (part "PINHD-1X1"))
    )
    (comp (ref "Q2")
      (value "DMG3415U-7")
      (footprint "eagle-import:SOT23-WIDE")
      (libsource (lib "eagle-import") (part "MOSFET-PWIDE"))
    )
    (comp (ref "Q3")
      (value "DMG3415U-7")
      (footprint "eagle-import:SOT23-WIDE")
      (libsource (lib "eagle-import") (part "MOSFET-PWIDE"))
    )
    (comp (ref "R12")
      (value "100K")
      (footprint "eagle-import:0805-NO")
      (libsource (lib "eagle-import") (part "RESISTOR0805_NOOUTLINE"))
    )
    (comp (ref "R13")
      (value "100K")
      (footprint "eagle-import:0805-NO")
      (libsource (lib "eagle-import") (part "RESISTOR0805_NOOUTLINE"))
    )
    (comp (ref "RELAY1")
      (value "G6SK-2_DC5")
      (footprint "eagle-import:G6SK2DC5")
      (fields (field (name "MANUFACTURER_PART_NUMBER") "G6SK-2 DC5"))
      (libsource (lib "eagle-import") (part "G6SK-2_DC5"))
    )
  )
  (nets
    (net (code "1") (name "+3V3") (class "Default")
      (node (ref "3V3") (pin "1") (pinfunction "1_1") (pintype "passive"))
      (node (ref "C10") (pin "1") (pinfunction "1_1") (pintype "passive"))
      (node (ref "C19") (pin "1") (pinfunction "1_1") (pintype "passive"))
      (node (ref "C5") (pin "1") (pinfunction "1_1") (pintype "passive"))
      (node (ref "C7") (pin "1") (pinfunction "1_1") (pintype "passive"))
      (node (ref "C8") (pin "1") (pinfunction "1_1") (pintype "passive"))
      (node (ref "LED1") (pin "1") (pinfunction "VDD_1") (pintype "power_in"))
      (node (ref "Q1") (pin "2") (pinfunction "S_2") (pintype "passive"))
      (node (ref "Q2") (pin "2") (pinfunction "S_2") (pintype "passive"))
      (node (ref "Q3") (pin "2") (pinfunction "S_2") (pintype "passive"))
      (node (ref "R1") (pin "1") (pinfunction "1_1") (pintype "passive"))
      (node (ref "R12") (pin "2") (pinfunction "2_2") (pintype "passive"))
      (node (ref "R13") (pin "2") (pinfunction "2_2") (pintype "passive"))
      (node (ref "R4") (pin "2") (pinfunction "2_2") (pintype "passive"))
      (node (ref "R5") (pin "1") (pinfunction "1_1") (pintype "passive"))
      (node (ref "R8") (pin "1") (pinfunction "1_1") (pintype "passive"))
      (node (ref "U1") (pin "3") (pinfunction "VDD_3") (pintype "power_in"))
      (node (ref "U2") (pin "5") (pinfunction "OUT_5") (pintype "power_in"))
      (node (ref "U5") (pin "17") (pinfunction "VDDIO_17") (pintype "power_in"))
      (node (ref "U5") (pin "36") (pinfunction "VDDIO_36") (pintype "power_in"))
      (node (ref "U5") (pin "44") (pinfunction "VDDIN_44") (pintype "power_in"))
      (node (ref "U5") (pin "6") (pinfunction "VDDA_6") (pintype "power_in"))
      (node (ref "U6") (pin "6_V_BCKP") (pinfunction "6_V_BCKP_6_V_BCKP") (pintype "bidirectional"))
    )
    (net (code "2") (name "3V3SW") (class "Default")
      (node (ref "3V3SW") (pin "1") (pinfunction "1_1") (pintype "passive"))
      (node (ref "C3") (pin "1") (pinfunction "1_1") (pintype "passive"))
      (node (ref "C9") (pin "1") (pinfunction "1_1") (pintype "passive"))
      (node (ref "Q1") (pin "3") (pinfunction "D_3") (pintype "passive"))
      (node (ref "U4") (pin "1") (pinfunction "VDD_1") (pintype "power_in"))
      (node (ref "U4") (pin "4") (pinfunction "VDDIO_4") (pintype "power_in"))
      (node (ref "U6") (pin "7_VCC_IO") (pinfunction "7_VCC_IO_7_VCC_IO") (pintype "power_in"))
      (node (ref "U6") (pin "8_VCC") (pinfunction "8_VCC_8_VCC") (pintype "power_in"))
    )
    (net (code "3") (name "9_V_RESET_N") (class "Default")
      (node (ref "U6") (pin "9_RESET_N") (pinfunction "9_V_RESET_N_9_RESET_N") (pintype "power_in"))
    )
    (net (code "4") (name "A0") (class "Default")
      (node (ref "R7") (pin "2") (pinfunction "2_2") (pintype "passive"))
      (node (ref "U5") (pin "3") (pinfunction "PA02/EINT2/AIN0/Y0/VOUT_3") (pintype "bidirectional"))
      (node (ref "U7") (pin "6") (pinfunction "VOUT_6") (pintype "passive"))
    )
    (net (code "5") (name "A1") (class "Default")
      (node (ref "R4") (pin "1") (pinfunction "1_1") (pintype "passive"))
      (node (ref "U3") (pin "5") (pinfunction "PGOOD_5") (pintype "output"))
      (node (ref "U5") (pin "7") (pinfunction "PB08/I8/AIN2/SERCOM4.0_7") (pintype "bidirectional"))
    )
    (net (code "6") (name "A2") (class "Default")
      (node (ref "U5") (pin "8") (pinfunction "PB09/I9/AIN3/SERCOM4.1_8") (pintype "bidirectional"))
    )
    (net (code "7") (name "A3") (class "Default")
      (node (ref "J1") (pin "12") (pinfunction "12_12") (pintype "bidirectional"))
      (node (ref "U5") (pin "9") (pinfunction "PA04/EINT4/VREFB/AIN4/SERCOM0.0_9") (pintype "bidirectional"))
    )
    (net (code "8") (name "A4") (class "Default")
      (node (ref "U5") (pin "10") (pinfunction "PA05/EINT5/AIN5/SERCOM0.1_10") (pintype "bidirectional"))
    )
    (net (code "9") (name "A5") (class "Default")
      (node (ref "R14") (pin "1") (pinfunction "1_1") (pintype "passive"))
      (node (ref "R17") (pin "1") (pinfunction "1_1") (pintype "passive"))
      (node (ref "U5") (pin "47") (pinfunction "PB02/I2/AIN10/SERCOM5.0_47") (pintype "bidirectional"))
    )
    (net (code "10") (name "AREF") (class "Default")
      (node (ref "C14") (pin "1") (pinfunction "1_1") (pintype "passive"))
      (node (ref "U5") (pin "4") (pinfunction "PA03/EINT3/VREFA/AIN1_4") (pintype "bidirectional"))
    )
    (net (code "11") (name "D+") (class "Default")
      (node (ref "CON1") (pin "D+") (pinfunction "D+_D+") (pintype "bidirectional"))
      (node (ref "U5") (pin "34") (pinfunction "PA25/I13/SERCOM3+5.3/D+_34") (pintype "bidirectional"))
    )
    (net (code "12") (name "D-") (class "Default")
      (node (ref "CON1") (pin "D-") (pinfunction "D-_D-") (pintype "bidirectional"))
      (node (ref "U5") (pin "33") (pinfunction "PA24/I12/SERCOM3+5.2/D-_33") (pintype "bidirectional"))
    )
    (net (code "13") (name "D0") (class "Default")
      (node (ref "U5") (pin "16") (pinfunction "PA11/I11/AIN19/SERCOM0+2.3/I2SF0_16") (pintype "bidirectional"))
      (node (ref "U6") (pin "2_TXD") (pinfunction "2_TXD_2_TXD") (pintype "bidirectional"))
    )
    (net (code "14") (name "D1") (class "Default")
      (node (ref "U5") (pin "15") (pinfunction "PA10/I10/AIN18/SERCOM0+2.2/I2SCK_15") (pintype "bidirectional"))
      (node (ref "U6") (pin "3_RXD") (pinfunction "3_RXD_3_RXD") (pintype "bidirectional"))
    )
    (net (code "15") (name "D2") (class "Default")
      (node (ref "SERCOM2_TX") (pin "1") (pinfunction "1_1") (pintype "passive"))
      (node (ref "U5") (pin "23") (pinfunction "PA14/I14/SERCOM2+4.2_23") (pintype "bidirectional"))
    )
    (net (code "16") (name "D3") (class "Default")
      (node (ref "Q3") (pin "1") (pinfunction "G_1") (pintype "passive"))
      (node (ref "R13") (pin "1") (pinfunction "1_1") (pintype "passive"))
      (node (ref "U5") (pin "14") (pinfunction "PA09/I2C/I9/AIN17/SERCOM0+2.1/I2SMC_14") (pintype "bidirectional"))
    )
    (net (code "17") (name "D5") (class "Default")
      (node (ref "SERCOM2_RX") (pin "1") (pinfunction "1_1") (pintype "passive"))
      (node (ref "U5") (pin "24") (pinfunction "PA15/I15/SERCOM3+4.3_24") (pintype "bidirectional"))
    )
    (net (code "18") (name "D6") (class "Default")
      (node (ref "J1") (pin "5") (pinfunction "5_5") (pintype "bidirectional"))
      (node (ref "U5") (pin "29") (pinfunction "PA20/I4/SERCOM3+5.2/I2SSC_29") (pintype "bidirectional"))
    )
    (net (code "19") (name "D7") (class "Default")
      (node (ref "Q2") (pin "1") (pinfunction "G_1") (pintype "passive"))
      (node (ref "R12") (pin "1") (pinfunction "1_1") (pintype "passive"))
      (node (ref "U5") (pin "30") (pinfunction "PA21/I5/SERCOM3+5.3/I2SFS0_30") (pintype "bidirectional"))
    )
    (net (code "20") (name "D8") (class "Default")
      (node (ref "R16") (pin "1") (pinfunction "1_1") (pintype "passive"))
      (node (ref "U3") (pin "4") (pinfunction "~{SHDN}_4") (pintype "input"))
      (node (ref "U5") (pin "11") (pinfunction "PA06/EINT6/AIN6/SERCOM0.2_11") (pintype "bidirectional"))
    )
    (net (code "21") (name "D9") (class "Default")
      (node (ref "R3") (pin "1") (pinfunction "1_1") (pintype "passive"))
      (node (ref "R6") (pin "2") (pinfunction "2_2") (pintype "passive"))
      (node (ref "U5") (pin "12") (pinfunction "PA07/I7/AIN7/SERCOM0.3/I2SD0_12") (pintype "bidirectional"))
    )
    (net (code "22") (name "D10") (class "Default")
      (node (ref "J1") (pin "6") (pinfunction "6_6") (pintype "bidirectional"))
      (node (ref "U5") (pin "27") (pinfunction "PA18/I2/SERCOM1+3.2_27") (pintype "bidirectional"))
    )
    (net (code "23") (name "D11") (class "Default")
      (node (ref "Q1") (pin "1") (pinfunction "G_1") (pintype "passive"))
      (node (ref "R1") (pin "2") (pinfunction "2_2") (pintype "passive"))
      (node (ref "U5") (pin "25") (pinfunction "PA16/I2C/I0/SERCOM1+3.0_25") (pintype "bidirectional"))
    )
    (net (code "24") (name "D12") (class "Default")
      (node (ref "J1") (pin "7") (pinfunction "7_7") (pintype "bidirectional"))
      (node (ref "U5") (pin "28") (pinfunction "PA19/I3/SERCOM1+3.3/I2SD0_28") (pintype "bidirectional"))
    )
    (net (code "25") (name "D13") (class "Default")
      (node (ref "LED1") (pin "4") (pinfunction "DIN_4") (pintype "input"))
      (node (ref "R10") (pin "1") (pinfunction "1_1") (pintype "passive"))
      (node (ref "U5") (pin "26") (pinfunction "PA17/I2C/I1/SERCOM1+3.1_26") (pintype "bidirectional"))
    )
    (net (code "26") (name "EXT_PWR") (class "Default")
      (node (ref "J1") (pin "1") (pinfunction "1_1") (pintype "bidirectional"))
      (node (ref "J1") (pin "2") (pinfunction "2_2") (pintype "bidirectional"))
      (node (ref "Q4") (pin "3") (pinfunction "D_3") (pintype "passive"))
    )
    (net (code "27") (name "GND") (class "Default")
      (node (ref "C1") (pin "2") (pinfunction "2_2") (pintype "passive"))
      (node (ref "C10") (pin "2") (pinfunction "2_2") (pintype "passive"))
      (node (ref "C12") (pin "-") (pinfunction "-_-") (pintype "passive"))
      (node (ref "C13") (pin "2") (pinfunction "2_2") (pintype "passive"))
      (node (ref "C14") (pin "2") (pinfunction "2_2") (pintype "passive"))
      (node (ref "C16") (pin "2") (pinfunction "2_2") (pintype "passive"))
      (node (ref "C17") (pin "2") (pinfunction "2_2") (pintype "passive"))
      (node (ref "C18") (pin "2") (pinfunction "2_2") (pintype "passive"))
      (node (ref "C19") (pin "2") (pinfunction "2_2") (pintype "passive"))
      (node (ref "C2") (pin "2") (pinfunction "2_2") (pintype "passive"))
      (node (ref "C3") (pin "2") (pinfunction "2_2") (pintype "passive"))
      (node (ref "C4") (pin "2") (pinfunction "2_2") (pintype "passive"))
      (node (ref "C5") (pin "2") (pinfunction "2_2") (pintype "passive"))
      (node (ref "C6") (pin "2") (pinfunction "2_2") (pintype "passive"))
      (node (ref "C7") (pin "2") (pinfunction "2_2") (pintype "passive"))
      (node (ref "C8") (pin "2") (pinfunction "2_2") (pintype "passive"))
      (node (ref "C9") (pin "2") (pinfunction "2_2") (pintype "passive"))
      (node (ref "CON1") (pin "BASE@1") (pinfunction "GND_BASE@1") (pintype "power_in"))
      (node (ref "CON1") (pin "BASE@2") (pinfunction "GND_BASE@2") (pintype "power_in"))
      (node (ref "CON1") (pin "GND") (pinfunction "GND_GND") (pintype "power_in"))
      (node (ref "CON1") (pin "SPRT@1") (pinfunction "GND_SPRT@1") (pintype "power_in"))
      (node (ref "CON1") (pin "SPRT@2") (pinfunction "GND_SPRT@2") (pintype "power_in"))
      (node (ref "CON1") (pin "SPRT@3") (pinfunction "GND_SPRT@3") (pintype "power_in"))
      (node (ref "CON1") (pin "SPRT@4") (pinfunction "GND_SPRT@4") (pintype "power_in"))
      (node (ref "D2") (pin "A") (pinfunction "A_A") (pintype "passive"))
      (node (ref "D3") (pin "A") (pinfunction "A_A") (pintype "passive"))
      (node (ref "GND") (pin "1") (pinfunction "1_1") (pintype "passive"))
      (node (ref "GND2") (pin "1") (pinfunction "1_1") (pintype "passive"))
      (node (ref "GND3") (pin "1") (pinfunction "1_1") (pintype "passive"))
      (node (ref "GND4") (pin "1") (pinfunction "1_1") (pintype "passive"))
      (node (ref "GND5") (pin "1") (pinfunction "1_1") (pintype "passive"))
      (node (ref "GND6") (pin "1") (pinfunction "1_1") (pintype "passive"))
      (node (ref "GNSS") (pin "G@1") (pinfunction "2_G@1") (pintype "passive"))
      (node (ref "GNSS") (pin "G@2") (pinfunction "2_G@2") (pintype "passive"))
      (node (ref "GNSS") (pin "G@3") (pinfunction "2_G@3") (pintype "passive"))
      (node (ref "GNSS") (pin "G@4") (pinfunction "2_G@4") (pintype "passive"))
      (node (ref "J1") (pin "13") (pinfunction "13_13") (pintype "bidirectional"))
      (node (ref "J1") (pin "14") (pinfunction "14_14") (pintype "bidirectional"))
      (node (ref "J1") (pin "15") (pinfunction "15_15") (pintype "bidirectional"))
      (node (ref "J1") (pin "18") (pinfunction "18_18") (pintype "bidirectional"))
      (node (ref "J1") (pin "3") (pinfunction "3_3") (pintype "bidirectional"))
      (node (ref "J1") (pin "4") (pinfunction "4_4") (pintype "bidirectional"))
      (node (ref "J1") (pin "8") (pinfunction "8_8") (pintype "bidirectional"))
      (node (ref "JP1") (pin "1") (pinfunction "1_1") (pintype "passive"))
      (node (ref "LED1") (pin "3") (pinfunction "VSS_3") (pintype "power_in"))
      (node (ref "LED2") (pin "C") (pinfunction "C_C") (pintype "passive"))
      (node (ref "Q5") (pin "E") (pinfunction "E_E") (pintype "passive"))
      (node (ref "R11") (pin "1") (pinfunction "1_1") (pintype "passive"))
      (node (ref "R16") (pin "2") (pinfunction "2_2") (pintype "passive"))
      (node (ref "R17") (pin "2") (pinfunction "2_2") (pintype "passive"))
      (node (ref "R2") (pin "1") (pinfunction "1_1") (pintype "passive"))
      (node (ref "R6") (pin "1") (pinfunction "1_1") (pintype "passive"))
      (node (ref "RELAY1") (pin "12") (pinfunction "COIL1-_12") (pintype "input"))
      (node (ref "RELAY1") (pin "7") (pinfunction "COIL2-_7") (pintype "input"))
      (node (ref "S1") (pin "P1") (pinfunction "P$1_P1") (pintype "bidirectional"))
      (node (ref "S2") (pin "P1") (pinfunction "P$1_P1") (pintype "bidirectional"))
      (node (ref "SW1") (pin "3") (pinfunction "3_3") (pintype "passive"))
      (node (ref "SW1") (pin "4") (pinfunction "4_4") (pintype "passive"))
      (node (ref "U1") (pin "2") (pinfunction "VSS_2") (pintype "power_in"))
      (node (ref "U2") (pin "2") (pinfunction "GND_2") (pintype "power_in"))
      (node (ref "U3") (pin "11") (pinfunction "GND_2_11") (pintype "passive"))
      (node (ref "U3") (pin "8") (pinfunction "GND_8") (pintype "passive"))
      (node (ref "U4") (pin "3") (pinfunction "GND_3") (pintype "power_in"))
      (node (ref "U5") (pin "18") (pinfunction "GND_18") (pintype "power_in"))
      (node (ref "U5") (pin "35") (pinfunction "GND_35") (pintype "power_in"))
      (node (ref "U5") (pin "42") (pinfunction "GND_42") (pintype "power_in"))
      (node (ref "U5") (pin "5") (pinfunction "GNDA_5") (pintype "power_in"))
      (node (ref "U5") (pin "THERMAL") (pinfunction "GND_THERMAL") (pintype "power_in"))
      (node (ref "U53") (pin "P$1") (pinfunction "P$1_P$1") (pintype "bidirectional"))
      (node (ref "U6") (pin "10_GND") (pinfunction "10_GND_10_GND") (pintype "power_in"))
      (node (ref "U6") (pin "12_GND") (pinfunction "12_GND_12_GND") (pintype "power_in"))
      (node (ref "U6") (pin "1_GND") (pinfunction "1_GND_1_GND") (pintype "power_in"))
      (node (ref "U7") (pin "4") (pinfunction "GND_4") (pintype "passive"))
    )
    (net (code "28") (name "GNDA") (class "Default")
      (node (ref "CON4") (pin "1") (pinfunction "GND_1") (pintype "passive"))
      (node (ref "CON4") (pin "2") (pinfunction "GND_2") (pintype "passive"))
      (node (ref "IRIDIUM") (pin "G@1") (pinfunction "2_G@1") (pintype "passive"))
      (node (ref "IRIDIUM") (pin "G@2") (pinfunction "2_G@2") (pintype "passive"))
      (node (ref "IRIDIUM") (pin "G@3") (pinfunction "2_G@3") (pintype "passive"))
      (node (ref "IRIDIUM") (pin "G@4") (pinfunction "2_G@4") (pintype "passive"))
    )
    (net (code "29") (name "GPS_ANT") (class "Default")
      (node (ref "GNSS") (pin "1") (pinfunction "1_1") (pintype "passive"))
      (node (ref "L1") (pin "2") (pinfunction "P$2_2") (pintype "passive"))
      (node (ref "U6") (pin "11_RF_IN") (pinfunction "11_RF_IN_11_RF_IN") (pintype "bidirectional"))
    )
    (net (code "30") (name "LTC3225_VOUT") (class "Default")
      (node (ref "C11") (pin "+") (pinfunction "+_+") (pintype "passive"))
      (node (ref "C16") (pin "1") (pinfunction "1_1") (pintype "passive"))
      (node (ref "Q4") (pin "2") (pinfunction "S_2") (pintype "passive"))
      (node (ref "R15") (pin "1") (pinfunction "1_1") (pintype "passive"))
      (node (ref "U3") (pin "10") (pinfunction "COUT_10") (pintype "output"))
    )
    (net (code "31") (name "MISO") (class "Default")
      (node (ref "MISO") (pin "1") (pinfunction "1_1") (pintype "passive"))
      (node (ref "U5") (pin "21") (pinfunction "PA12/I12/I2C/SERCOM2+4.0_21") (pintype "bidirectional"))
    )
    (net (code "32") (name "MOSI") (class "Default")
      (node (ref "MOSI") (pin "1") (pinfunction "1_1") (pintype "passive"))
      (node (ref "U5") (pin "19") (pinfunction "PB10/I10/SERCOM4.2/I2SMC_19") (pintype "bidirectional"))
    )
    (net (code "33") (name "Net-(BAT--Pad1)") (class "Default")
      (node (ref "BAT-") (pin "1") (pinfunction "1_1") (pintype "passive"))
      (node (ref "BAT3") (pin "GND@1") (pinfunction "-_GND@1") (pintype "power_in"))
      (node (ref "BAT3") (pin "GND@2") (pinfunction "-_GND@2") (pintype "power_in"))
      (node (ref "BAT6") (pin "GND@1") (pinfunction "-_GND@1") (pintype "power_in"))
      (node (ref "BAT6") (pin "GND@2") (pinfunction "-_GND@2") (pintype "power_in"))
      (node (ref "U53") (pin "P$2") (pinfunction "P$2_P$2") (pintype "bidirectional"))
    )
    (net (code "34") (name "Net-(BAT1---PadGND@1)") (class "Default")
      (node (ref "BAT1") (pin "GND@1") (pinfunction "-_GND@1") (pintype "power_in"))
      (node (ref "BAT1") (pin "GND@2") (pinfunction "-_GND@2") (pintype "power_in"))
      (node (ref "BAT2") (pin "PWR@1") (pinfunction "+_PWR@1") (pintype "power_in"))
      (node (ref "BAT2") (pin "PWR@2") (pinfunction "+_PWR@2") (pintype "power_in"))
    )
    (net (code "35") (name "Net-(BAT2---PadGND@1)") (class "Default")
      (node (ref "BAT2") (pin "GND@1") (pinfunction "-_GND@1") (pintype "power_in"))
      (node (ref "BAT2") (pin "GND@2") (pinfunction "-_GND@2") (pintype "power_in"))
      (node (ref "BAT3") (pin "PWR@1") (pinfunction "+_PWR@1") (pintype "power_in"))
      (node (ref "BAT3") (pin "PWR@2") (pinfunction "+_PWR@2") (pintype "power_in"))
    )
    (net (code "36") (name "Net-(BAT4---PadGND@1)") (class "Default")
      (node (ref "BAT4") (pin "GND@1") (pinfunction "-_GND@1") (pintype "power_in"))
      (node (ref "BAT4") (pin "GND@2") (pinfunction "-_GND@2") (pintype "power_in"))
      (node (ref "BAT5") (pin "PWR@1") (pinfunction "+_PWR@1") (pintype "power_in"))
      (node (ref "BAT5") (pin "PWR@2") (pinfunction "+_PWR@2") (pintype "power_in"))
    )
    (net (code "37") (name "Net-(BAT5---PadGND@1)") (class "Default")
      (node (ref "BAT5") (pin "GND@1") (pinfunction "-_GND@1") (pintype "power_in"))
      (node (ref "BAT5") (pin "GND@2") (pinfunction "-_GND@2") (pintype "power_in"))
      (node (ref "BAT6") (pin "PWR@1") (pinfunction "+_PWR@1") (pintype "power_in"))
      (node (ref "BAT6") (pin "PWR@2") (pinfunction "+_PWR@2") (pintype "power_in"))
    )
    (net (code "38") (name "Net-(CON1-PadVBUS)") (class "Default")
      (node (ref "CON1") (pin "VBUS") (pinfunction "VBUS_VBUS") (pintype "power_in"))
      (node (ref "D4") (pin "A") (pinfunction "A_A") (pintype "passive"))
    )
    (net (code "39") (name "Net-(CON4-SIGNAL)") (class "Default")
      (node (ref "CON4") (pin "3") (pinfunction "SIGNAL_3") (pintype "passive"))
      (node (ref "IRIDIUM") (pin "1") (pinfunction "1_1") (pintype "passive"))
    )
    (net (code "40") (name "Net-(JP2-Pad1)") (class "Default")
      (node (ref "JP2") (pin "1") (pinfunction "1_1") (pintype "passive"))
      (node (ref "R11") (pin "2") (pinfunction "2_2") (pintype "passive"))
    )
    (net (code "41") (name "Net-(JP2-Pad3)") (class "Default")
      (node (ref "JP2") (pin "3") (pinfunction "3_3") (pintype "passive"))
      (node (ref "R2") (pin "2") (pinfunction "2_2") (pintype "passive"))
    )
    (net (code "42") (name "Net-(L1-P$1)") (class "Default")
      (node (ref "C18") (pin "1") (pinfunction "1_1") (pintype "passive"))
      (node (ref "L1") (pin "1") (pinfunction "P$1_1") (pintype "passive"))
      (node (ref "R9") (pin "1") (pinfunction "1_1") (pintype "passive"))
    )
    (net (code "43") (name "Net-(LED2-PadA)") (class "Default")
      (node (ref "LED2") (pin "A") (pinfunction "A_A") (pintype "passive"))
      (node (ref "R10") (pin "2") (pinfunction "2_2") (pintype "passive"))
    )
    (net (code "44") (name "Net-(Q4-G)") (class "Default")
      (node (ref "Q4") (pin "1") (pinfunction "G_1") (pintype "passive"))
      (node (ref "Q5") (pin "C") (pinfunction "C_C") (pintype "passive"))
      (node (ref "R15") (pin "2") (pinfunction "2_2") (pintype "passive"))
    )
    (net (code "45") (name "Net-(Q5-PadB)") (class "Default")
      (node (ref "Q5") (pin "B") (pinfunction "B_B") (pintype "passive"))
      (node (ref "R14") (pin "2") (pinfunction "2_2") (pintype "passive"))
    )
    (net (code "46") (name "Net-(RELAY1-COM(1))") (class "Default")
      (node (ref "COM1") (pin "1") (pinfunction "1_1") (pintype "passive"))
      (node (ref "RELAY1") (pin "4") (pinfunction "COM(1)_4") (pintype "input"))
    )
    (net (code "47") (name "Net-(RELAY1-COM(2))") (class "Default")
      (node (ref "COM2") (pin "1") (pinfunction "1_1") (pintype "passive"))
      (node (ref "RELAY1") (pin "9") (pinfunction "COM(2)_9") (pintype "input"))
    )
    (net (code "48") (name "Net-(RELAY1-NC(1))") (class "Default")
      (node (ref "NC1") (pin "1") (pinfunction "1_1") (pintype "passive"))
      (node (ref "RELAY1") (pin "3") (pinfunction "NC(1)_3") (pintype "input"))
    )
    (net (code "49") (name "Net-(RELAY1-NC(2))") (class "Default")
      (node (ref "NC2") (pin "1") (pinfunction "1_1") (pintype "passive"))
      (node (ref "RELAY1") (pin "10") (pinfunction "NC(2)_10") (pintype "input"))
    )
    (net (code "50") (name "Net-(RELAY1-NO(1))") (class "Default")
      (node (ref "NO1") (pin "1") (pinfunction "1_1") (pintype "passive"))
      (node (ref "RELAY1") (pin "5") (pinfunction "NO(1)_5") (pintype "input"))
    )
    (net (code "51") (name "Net-(RELAY1-NO(2))") (class "Default")
      (node (ref "NO2") (pin "1") (pinfunction "1_1") (pintype "passive"))
      (node (ref "RELAY1") (pin "8") (pinfunction "NO(2)_8") (pintype "input"))
    )
    (net (code "52") (name "Net-(U3-C+)") (class "Default")
      (node (ref "C15") (pin "1") (pinfunction "1_1") (pintype "passive"))
      (node (ref "U3") (pin "1") (pinfunction "C+_1") (pintype "passive"))
    )
    (net (code "53") (name "Net-(U3-C-)") (class "Default")
      (node (ref "C15") (pin "2") (pinfunction "2_2") (pintype "passive"))
      (node (ref "U3") (pin "2") (pinfunction "C-_2") (pintype "passive"))
    )
    (net (code "54") (name "Net-(U3-CX)") (class "Default")
      (node (ref "C11") (pin "-") (pinfunction "-_-") (pintype "passive"))
      (node (ref "C12") (pin "+") (pinfunction "+_+") (pintype "passive"))
      (node (ref "U3") (pin "3") (pinfunction "CX_3") (pintype "passive"))
    )
    (net (code "55") (name "Net-(U3-PROG)") (class "Default")
      (node (ref "JP2") (pin "2") (pinfunction "2_2") (pintype "passive"))
      (node (ref "U3") (pin "7") (pinfunction "PROG_7") (pintype "input"))
    )
    (net (code "56") (name "Net-(U3-VSEL)") (class "Default")
      (node (ref "JP1") (pin "2") (pinfunction "2_2") (pintype "passive"))
      (node (ref "U3") (pin "6") (pinfunction "VSEL_6") (pintype "input"))
    )
    (net (code "57") (name "Net-(U4-CAP)") (class "Default")
      (node (ref "C13") (pin "1") (pinfunction "1_1") (pintype "passive"))
      (node (ref "U4") (pin "2") (pinfunction "CAP_2") (pintype "power_in"))
    )
    (net (code "58") (name "Net-(U5-PA00{slash}EINT0{slash}SERCOM1.0)") (class "Default")
      (node (ref "C2") (pin "1") (pinfunction "1_1") (pintype "passive"))
      (node (ref "U5") (pin "1") (pinfunction "PA00/EINT0/SERCOM1.0_1") (pintype "bidirectional"))
      (node (ref "X1") (pin "P$1") (pinfunction "P$1_P$1") (pintype "bidirectional"))
    )
    (net (code "59") (name "Net-(U5-PA01{slash}EINT1{slash}SERCOM1.1)") (class "Default")
      (node (ref "C4") (pin "1") (pinfunction "1_1") (pintype "passive"))
      (node (ref "U5") (pin "2") (pinfunction "PA01/EINT1/SERCOM1.1_2") (pintype "bidirectional"))
      (node (ref "X1") (pin "P$2") (pinfunction "P$2_P$2") (pintype "bidirectional"))
    )
    (net (code "60") (name "Net-(U5-VDDCORE)") (class "Default")
      (node (ref "C1") (pin "1") (pinfunction "1_1") (pintype "passive"))
      (node (ref "U5") (pin "43") (pinfunction "VDDCORE_43") (pintype "power_in"))
    )
    (net (code "61") (name "RESET_RELAY") (class "Default")
      (node (ref "D3") (pin "C") (pinfunction "C_C") (pintype "passive"))
      (node (ref "Q3") (pin "3") (pinfunction "D_3") (pintype "passive"))
      (node (ref "RELAY1") (pin "6") (pinfunction "COIL2+_6") (pintype "input"))
    )
    (net (code "62") (name "SCK") (class "Default")
      (node (ref "SCK") (pin "1") (pinfunction "1_1") (pintype "passive"))
      (node (ref "U5") (pin "20") (pinfunction "PB11/I11/SERCOM4.3/I2SCL_20") (pintype "bidirectional"))
    )
    (net (code "63") (name "SCL") (class "Default")
      (node (ref "R8") (pin "2") (pinfunction "2_2") (pintype "passive"))
      (node (ref "SCL") (pin "1") (pinfunction "1_1") (pintype "passive"))
      (node (ref "U4") (pin "8") (pinfunction "SCL_8") (pintype "bidirectional"))
      (node (ref "U5") (pin "32") (pinfunction "PA23/I2C/I7/SERCOM3+5.1/SOF_32") (pintype "bidirectional"))
    )
    (net (code "64") (name "SDA") (class "Default")
      (node (ref "R5") (pin "2") (pinfunction "2_2") (pintype "passive"))
      (node (ref "SDA") (pin "1") (pinfunction "1_1") (pintype "passive"))
      (node (ref "U4") (pin "7") (pinfunction "SDA_7") (pintype "bidirectional"))
      (node (ref "U5") (pin "31") (pinfunction "PA22/I2C/I6/SERCOM3+5.0_31") (pintype "bidirectional"))
    )
    (net (code "65") (name "SD_CS") (class "Default")
      (node (ref "CS") (pin "1") (pinfunction "1_1") (pintype "passive"))
      (node (ref "U5") (pin "13") (pinfunction "PA08/I2C/AIN16/SERCOM0+2.0/I2SD1_13") (pintype "bidirectional"))
    )
    (net (code "66") (name "SET_RELAY") (class "Default")
      (node (ref "D2") (pin "C") (pinfunction "C_C") (pintype "passive"))
      (node (ref "Q2") (pin "3") (pinfunction "D_3") (pintype "passive"))
      (node (ref "RELAY1") (pin "1") (pinfunction "COIL1+_1") (pintype "input"))
    )
    (net (code "67") (name "SWCLK") (class "Default")
      (node (ref "SWCLK") (pin "1") (pinfunction "1_1") (pintype "passive"))
      (node (ref "U5") (pin "45") (pinfunction "PA30/I10/SECOM1.2/SWCLK_45") (pintype "bidirectional"))
    )
    (net (code "68") (name "SWDIO") (class "Default")
      (node (ref "SWDIO") (pin "1") (pinfunction "1_1") (pintype "passive"))
      (node (ref "U5") (pin "46") (pinfunction "PA31/I11/SECOM1.3/SWDIO_46") (pintype "bidirectional"))
    )
    (net (code "69") (name "VBAT") (class "Default")
      (node (ref "BAT1") (pin "PWR@1") (pinfunction "+_PWR@1") (pintype "power_in"))
      (node (ref "BAT1") (pin "PWR@2") (pinfunction "+_PWR@2") (pintype "power_in"))
      (node (ref "D1") (pin "A") (pinfunction "A_A") (pintype "passive"))
    )
    (net (code "70") (name "VBAT1") (class "Default")
      (node (ref "BAT4") (pin "PWR@1") (pinfunction "+_PWR@1") (pintype "power_in"))
      (node (ref "BAT4") (pin "PWR@2") (pinfunction "+_PWR@2") (pintype "power_in"))
      (node (ref "D5") (pin "A") (pinfunction "A_A") (pintype "passive"))
    )
    (net (code "71") (name "VBUS") (class "Default")
      (node (ref "C17") (pin "1") (pinfunction "1_1") (pintype "passive"))
      (node (ref "C6") (pin "1") (pinfunction "1_1") (pintype "passive"))
      (node (ref "D1") (pin "C") (pinfunction "C_C") (pintype "passive"))
      (node (ref "D4") (pin "C") (pinfunction "C_C") (pintype "passive"))
      (node (ref "D5") (pin "C") (pinfunction "C_C") (pintype "passive"))
      (node (ref "JP1") (pin "3") (pinfunction "3_3") (pintype "passive"))
      (node (ref "R3") (pin "2") (pinfunction "2_2") (pintype "passive"))
      (node (ref "R7") (pin "1") (pinfunction "1_1") (pintype "passive"))
      (node (ref "U2") (pin "1") (pinfunction "IN_1") (pintype "power_in"))
      (node (ref "U2") (pin "3") (pinfunction "EN_3") (pintype "input"))
      (node (ref "U3") (pin "9") (pinfunction "VIN_9") (pintype "power_in"))
      (node (ref "VBUS") (pin "1") (pinfunction "1_1") (pintype "passive"))
    )
    (net (code "72") (name "VCC_RF") (class "Default")
      (node (ref "R9") (pin "2") (pinfunction "2_2") (pintype "passive"))
      (node (ref "U6") (pin "14_VCC_RF") (pinfunction "14_VCC_RF_14_VCC_RF") (pintype "bidirectional"))
    )
    (net (code "73") (name "unconnected-(CON1-PadID)") (class "Default")
      (node (ref "CON1") (pin "ID") (pinfunction "ID_ID") (pintype "bidirectional"))
    )
    (net (code "74") (name "unconnected-(J1-Pad9)") (class "Default")
      (node (ref "J1") (pin "9") (pinfunction "9_9") (pintype "bidirectional"))
    )
    (net (code "75") (name "unconnected-(J1-Pad10)") (class "Default")
      (node (ref "J1") (pin "10") (pinfunction "10_10") (pintype "bidirectional"))
    )
    (net (code "76") (name "unconnected-(J1-Pad11)") (class "Default")
      (node (ref "J1") (pin "11") (pinfunction "11_11") (pintype "bidirectional"))
    )
    (net (code "77") (name "unconnected-(J1-Pad16)") (class "Default")
      (node (ref "J1") (pin "16") (pinfunction "16_16") (pintype "bidirectional"))
    )
    (net (code "78") (name "unconnected-(J1-Pad17)") (class "Default")
      (node (ref "J1") (pin "17") (pinfunction "17_17") (pintype "bidirectional"))
    )
    (net (code "79") (name "unconnected-(J1-Pad19)") (class "Default")
      (node (ref "J1") (pin "19") (pinfunction "19_19") (pintype "bidirectional"))
    )
    (net (code "80") (name "unconnected-(J1-Pad20)") (class "Default")
      (node (ref "J1") (pin "20") (pinfunction "20_20") (pintype "bidirectional"))
    )
    (net (code "81") (name "unconnected-(LED1-DOUT-Pad2)") (class "Default")
      (node (ref "LED1") (pin "2") (pinfunction "DOUT_2") (pintype "output"))
    )
    (net (code "82") (name "unconnected-(U2-P4-Pad4)") (class "Default")
      (node (ref "U2") (pin "4") (pinfunction "P4_4") (pintype "bidirectional"))
    )
    (net (code "83") (name "unconnected-(U4-INT1-Pad6)") (class "Default")
      (node (ref "U4") (pin "6") (pinfunction "INT1_6") (pintype "output"))
    )
    (net (code "84") (name "unconnected-(U4-INT2-Pad5)") (class "Default")
      (node (ref "U4") (pin "5") (pinfunction "INT2_5") (pintype "output"))
    )
    (net (code "85") (name "unconnected-(U5-PA13{slash}I13{slash}I2C{slash}SERCOM2+4.1-Pad22)") (class "Default")
      (node (ref "U5") (pin "22") (pinfunction "PA13/I13/I2C/SERCOM2+4.1_22") (pintype "bidirectional"))
    )
    (net (code "86") (name "unconnected-(U5-PA27{slash}I15-Pad39)") (class "Default")
      (node (ref "U5") (pin "39") (pinfunction "PA27/I15_39") (pintype "bidirectional"))
    )
    (net (code "87") (name "unconnected-(U5-PA28{slash}I8-Pad41)") (class "Default")
      (node (ref "U5") (pin "41") (pinfunction "PA28/I8_41") (pintype "bidirectional"))
    )
    (net (code "88") (name "unconnected-(U5-PB03{slash}I3{slash}AIN11{slash}SERCOM5.1-Pad48)") (class "Default")
      (node (ref "U5") (pin "48") (pinfunction "PB03/I3/AIN11/SERCOM5.1_48") (pintype "bidirectional"))
    )
    (net (code "89") (name "unconnected-(U5-PB22{slash}I6{slash}SERCOM5.2-Pad37)") (class "Default")
      (node (ref "U5") (pin "37") (pinfunction "PB22/I6/SERCOM5.2_37") (pintype "bidirectional"))
    )
    (net (code "90") (name "unconnected-(U5-PB23{slash}I7{slash}SERCOM5.3-Pad38)") (class "Default")
      (node (ref "U5") (pin "38") (pinfunction "PB23/I7/SERCOM5.3_38") (pintype "bidirectional"))
    )
    (net (code "91") (name "unconnected-(U6-13_LNA_EN{slash}RES-Pad13_LNA_EN)") (class "Default")
      (node (ref "U6") (pin "13_LNA_EN") (pinfunction "13_LNA_EN/RES_13_LNA_EN") (pintype "bidirectional"))
    )
    (net (code "92") (name "unconnected-(U6-15_RES{slash}V_ANT-Pad15_V_ANT{slash}RESERVED)") (class "Default")
      (node (ref "U6") (pin "15_V_ANT/RESERVED") (pinfunction "15_RES/V_ANT_15_V_ANT/RESERVED") (pintype "bidirectional"))
    )
    (net (code "93") (name "unconnected-(U6-Pad4_TIMEPULSE)") (class "Default")
      (node (ref "U6") (pin "4_TIMEPULSE") (pinfunction "4_TIMEPULSE_4_TIMEPULSE") (pintype "bidirectional"))
    )
    (net (code "94") (name "unconnected-(U6-Pad5_EXTINT)") (class "Default")
      (node (ref "U6") (pin "5_EXTINT") (pinfunction "5_EXTINT_5_EXTINT") (pintype "bidirectional"))
    )
    (net (code "95") (name "unconnected-(U6-Pad16_SDA)") (class "Default")
      (node (ref "U6") (pin "16_SDA") (pinfunction "16_SDA_16_SDA") (pintype "bidirectional"))
    )
    (net (code "96") (name "unconnected-(U6-Pad17_SCL)") (class "Default")
      (node (ref "U6") (pin "17_SCL") (pinfunction "17_SCL_17_SCL") (pintype "bidirectional"))
    )
    (net (code "97") (name "unconnected-(U6-Pad18_SAFEBOOT_N)") (class "Default")
      (node (ref "U6") (pin "18_SAFEBOOT_N") (pinfunction "18_SAFEBOOT_N_18_SAFEBOOT_N") (pintype "bidirectional"))
    )
    (net (code "98") (name "unconnected-(U53-PadP$3)") (class "Default")
      (node (ref "U53") (pin "P$3") (pinfunction "P$3_P$3") (pintype "bidirectional"))
    )
    (net (code "99") (name "~{RESET}") (class "Default")
      (node (ref "RST") (pin "1") (pinfunction "1_1") (pintype "passive"))
      (node (ref "SW1") (pin "1") (pinfunction "1_1") (pintype "passive"))
      (node (ref "SW1") (pin "2") (pinfunction "2_2") (pintype "passive"))
      (node (ref "U1") (pin "1") (pinfunction "VOUT_1") (pintype "output"))
      (node (ref "U5") (pin "40") (pinfunction "/RESET_40") (pintype "bidirectional"))
    )
  )
)
